# STlink-V3EC.net
KiCad netlist of a schematic drawn in Altium Designer
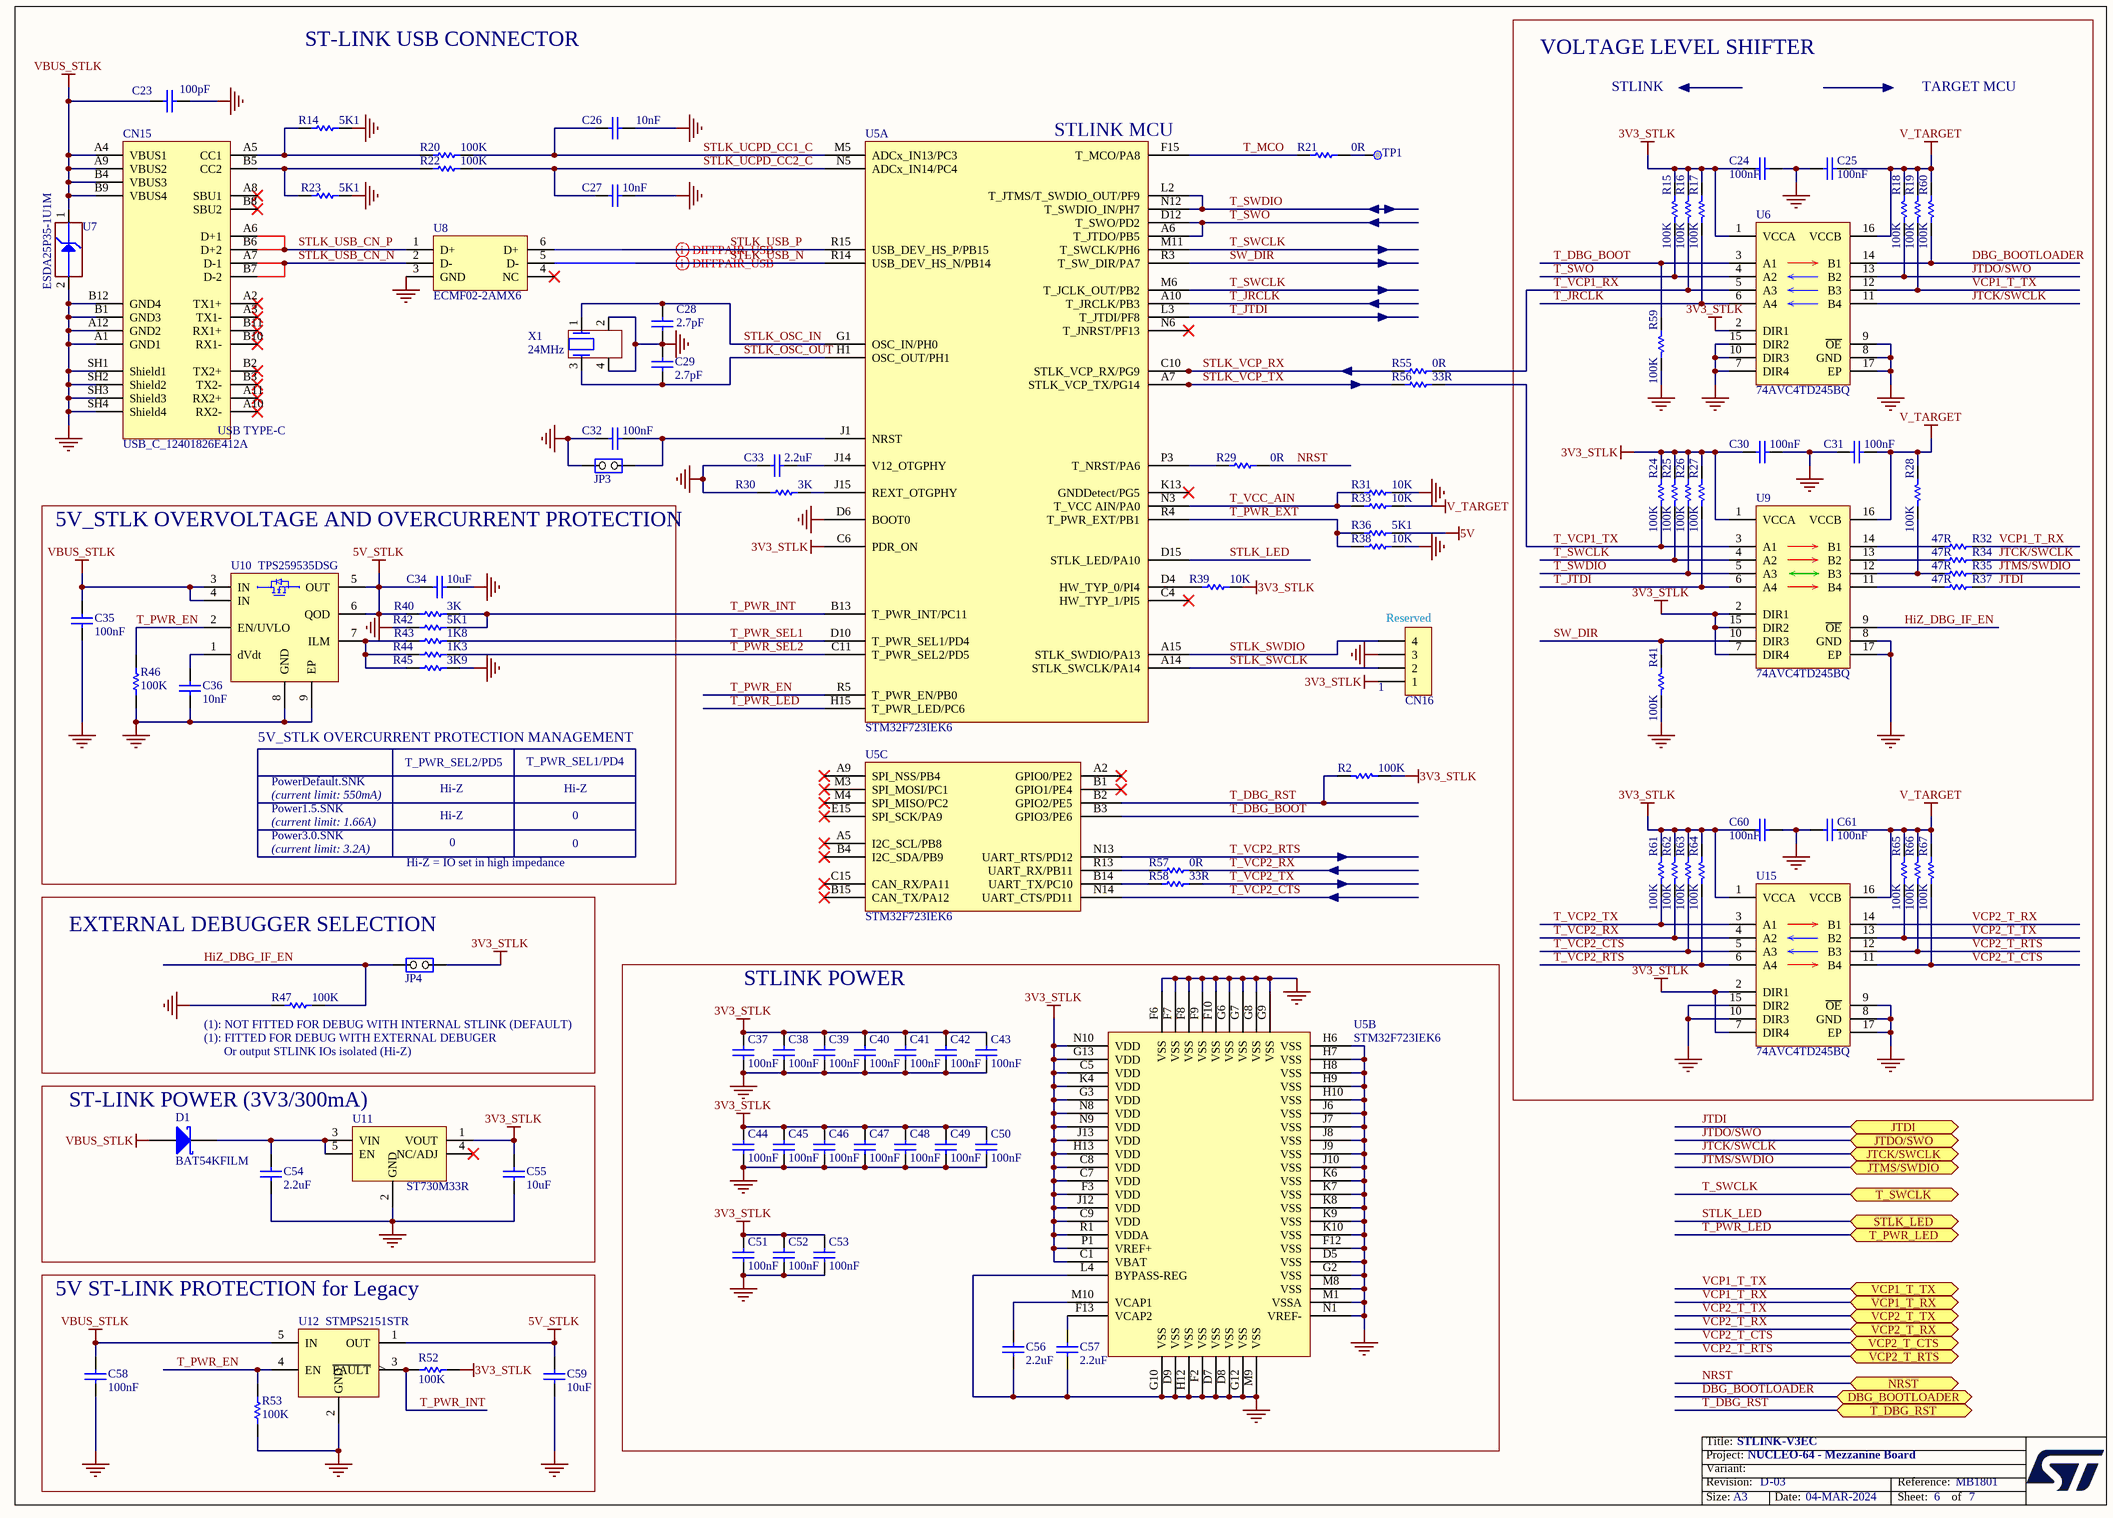
[diagram p0: STlink-V3EC.SchDoc]

(export (version "E")
  (design (tool "Eeschema 10.0.6"))
  (components
    (comp (ref "C23")
      (value "100pF")
      (footprint "MCD_PARTS:C0402")
      (description "Capacitor, MLCC, 100pF, 50V, NPO, +/-5%, 0402, T=0.5mm")
      (fields (field (name "INTERNAL_PART_NUMBER") "MCD-00205") (field (name "MANUFACTURER") "YAGEO"))
      (libsource (lib "MCD_PARTS_database") (part "Capacitor"))
    )
    (comp (ref "C24")
      (value "100nF")
      (footprint "MCD_PARTS:C0402")
      (description "Capacitor, MLCC, 100nF, 16V, X7R, 10%, 0402, T=0.5mm")
      (fields
        (field (name "INTERNAL_PART_NUMBER") "MCD-00006")
        (field (name "MANUFACTURER_PART_NUMBER") "CC0402KRX7R7BB104")
        (field (name "PROVIDED_BY") "SUBCO")
      )
      (libsource (lib "MCD_PARTS_database") (part "Capacitor"))
    )
    (comp (ref "C25")
      (value "100nF")
      (footprint "MCD_PARTS:C0402")
      (description "Capacitor, MLCC, 100nF, 16V, X7R, 10%, 0402, T=0.5mm")
      (fields
        (field (name "INTERNAL_PART_NUMBER") "MCD-00006")
        (field (name "MANUFACTURER_PART_NUMBER") "CC0402KRX7R7BB104")
        (field (name "PROVIDED_BY") "SUBCO")
      )
      (libsource (lib "MCD_PARTS_database") (part "Capacitor"))
    )
    (comp (ref "C26")
      (value "10nF")
      (footprint "MCD_PARTS:C0402")
      (description "Capacitor, MLCC, 10nF, 50V, X7R, +/-10%, 0402, T=0.5mm")
      (fields (field (name "INTERNAL_PART_NUMBER") "MCD-02198") (field (name "MANUFACTURER") "YAGEO"))
      (libsource (lib "MCD_PARTS_database") (part "Capacitor"))
    )
    (comp (ref "C27")
      (value "10nF")
      (footprint "MCD_PARTS:C0402")
      (description "Capacitor, MLCC, 10nF, 50V, X7R, +/-10%, 0402, T=0.5mm")
      (fields (field (name "INTERNAL_PART_NUMBER") "MCD-02198") (field (name "MANUFACTURER") "YAGEO"))
      (libsource (lib "MCD_PARTS_database") (part "Capacitor"))
    )
    (comp (ref "C28")
      (value "2.7pF")
      (footprint "MCD_PARTS:C0402")
      (description "Capacitor, MLCC, 2.7pF, 50V, NPO, +/-0.1pF, 0402, T=0.5mm")
      (fields (field (name "INTERNAL_PART_NUMBER") "MCD-01774") (field (name "MANUFACTURER") "YAGEO"))
      (libsource (lib "MCD_PARTS_database") (part "Capacitor"))
    )
    (comp (ref "C29")
      (value "2.7pF")
      (footprint "MCD_PARTS:C0402")
      (description "Capacitor, MLCC, 2.7pF, 50V, NPO, +/-0.1pF, 0402, T=0.5mm")
      (fields (field (name "INTERNAL_PART_NUMBER") "MCD-01774") (field (name "MANUFACTURER") "YAGEO"))
      (libsource (lib "MCD_PARTS_database") (part "Capacitor"))
    )
    (comp (ref "C30")
      (value "100nF")
      (footprint "MCD_PARTS:C0402")
      (description "Capacitor, MLCC, 100nF, 16V, X7R, 10%, 0402, T=0.5mm")
      (fields
        (field (name "INTERNAL_PART_NUMBER") "MCD-00006")
        (field (name "MANUFACTURER_PART_NUMBER") "CC0402KRX7R7BB104")
        (field (name "PROVIDED_BY") "SUBCO")
      )
      (libsource (lib "MCD_PARTS_database") (part "Capacitor"))
    )
    (comp (ref "C31")
      (value "100nF")
      (footprint "MCD_PARTS:C0402")
      (description "Capacitor, MLCC, 100nF, 16V, X7R, 10%, 0402, T=0.5mm")
      (fields
        (field (name "INTERNAL_PART_NUMBER") "MCD-00006")
        (field (name "MANUFACTURER_PART_NUMBER") "CC0402KRX7R7BB104")
        (field (name "PROVIDED_BY") "SUBCO")
      )
      (libsource (lib "MCD_PARTS_database") (part "Capacitor"))
    )
    (comp (ref "C32")
      (value "100nF")
      (footprint "MCD_PARTS:C0402")
      (description "Capacitor, MLCC, 100nF, 16V, X7R, 10%, 0402, T=0.5mm")
      (fields
        (field (name "INTERNAL_PART_NUMBER") "MCD-00006")
        (field (name "MANUFACTURER_PART_NUMBER") "CC0402KRX7R7BB104")
        (field (name "PROVIDED_BY") "SUBCO")
      )
      (libsource (lib "MCD_PARTS_database") (part "Capacitor"))
    )
    (comp (ref "C33")
      (value "2.2uF")
      (footprint "MCD_PARTS:C0402")
      (description "Capacitor, MLCC, 2.2uF, 6.3V, X5R, +/-10%, 0402, T=0.5mm")
      (fields (field (name "INTERNAL_PART_NUMBER") "MCD-02606") (field (name "MANUFACTURER") "YAGEO"))
      (libsource (lib "MCD_PARTS_database") (part "Capacitor"))
    )
    (comp (ref "C34")
      (value "10uF")
      (footprint "MCD_PARTS:C0603")
      (description "Capacitor, MLCC, 10uF, 10V, X5R, +/-10%, 0603, T=0.8mm")
      (fields (field (name "INTERNAL_PART_NUMBER") "MCD-00099") (field (name "MANUFACTURER") "MURATA"))
      (libsource (lib "MCD_PARTS_database") (part "Capacitor"))
    )
    (comp (ref "C35")
      (value "100nF")
      (footprint "MCD_PARTS:C0402")
      (description "Capacitor, MLCC, 100nF, 25V, X7R, +/-10%, 0402, T=0.5mm")
      (fields (field (name "INTERNAL_PART_NUMBER") "MCD-02355") (field (name "MANUFACTURER") "WALSIN"))
      (libsource (lib "MCD_PARTS_database") (part "Capacitor"))
    )
    (comp (ref "C36")
      (value "10nF")
      (footprint "MCD_PARTS:C0402")
      (description "Capacitor, MLCC, 10nF, 50V, X7R, +/-10%, 0402, T=0.5mm")
      (fields (field (name "INTERNAL_PART_NUMBER") "MCD-02198") (field (name "MANUFACTURER") "YAGEO"))
      (libsource (lib "MCD_PARTS_database") (part "Capacitor"))
    )
    (comp (ref "C37")
      (value "100nF")
      (footprint "MCD_PARTS:C0402")
      (description "Capacitor, MLCC, 100nF, 16V, X7R, 10%, 0402, T=0.5mm")
      (fields
        (field (name "INTERNAL_PART_NUMBER") "MCD-00006")
        (field (name "MANUFACTURER_PART_NUMBER") "CC0402KRX7R7BB104")
        (field (name "PROVIDED_BY") "SUBCO")
      )
      (libsource (lib "MCD_PARTS_database") (part "Capacitor"))
    )
    (comp (ref "C38")
      (value "100nF")
      (footprint "MCD_PARTS:C0402")
      (description "Capacitor, MLCC, 100nF, 16V, X7R, 10%, 0402, T=0.5mm")
      (fields
        (field (name "INTERNAL_PART_NUMBER") "MCD-00006")
        (field (name "MANUFACTURER_PART_NUMBER") "CC0402KRX7R7BB104")
        (field (name "PROVIDED_BY") "SUBCO")
      )
      (libsource (lib "MCD_PARTS_database") (part "Capacitor"))
    )
    (comp (ref "C39")
      (value "100nF")
      (footprint "MCD_PARTS:C0402")
      (description "Capacitor, MLCC, 100nF, 16V, X7R, 10%, 0402, T=0.5mm")
      (fields
        (field (name "INTERNAL_PART_NUMBER") "MCD-00006")
        (field (name "MANUFACTURER_PART_NUMBER") "CC0402KRX7R7BB104")
        (field (name "PROVIDED_BY") "SUBCO")
      )
      (libsource (lib "MCD_PARTS_database") (part "Capacitor"))
    )
    (comp (ref "C40")
      (value "100nF")
      (footprint "MCD_PARTS:C0402")
      (description "Capacitor, MLCC, 100nF, 16V, X7R, 10%, 0402, T=0.5mm")
      (fields
        (field (name "INTERNAL_PART_NUMBER") "MCD-00006")
        (field (name "MANUFACTURER_PART_NUMBER") "CC0402KRX7R7BB104")
        (field (name "PROVIDED_BY") "SUBCO")
      )
      (libsource (lib "MCD_PARTS_database") (part "Capacitor"))
    )
    (comp (ref "C41")
      (value "100nF")
      (footprint "MCD_PARTS:C0402")
      (description "Capacitor, MLCC, 100nF, 16V, X7R, 10%, 0402, T=0.5mm")
      (fields
        (field (name "INTERNAL_PART_NUMBER") "MCD-00006")
        (field (name "MANUFACTURER_PART_NUMBER") "CC0402KRX7R7BB104")
        (field (name "PROVIDED_BY") "SUBCO")
      )
      (libsource (lib "MCD_PARTS_database") (part "Capacitor"))
    )
    (comp (ref "C42")
      (value "100nF")
      (footprint "MCD_PARTS:C0402")
      (description "Capacitor, MLCC, 100nF, 16V, X7R, 10%, 0402, T=0.5mm")
      (fields
        (field (name "INTERNAL_PART_NUMBER") "MCD-00006")
        (field (name "MANUFACTURER_PART_NUMBER") "CC0402KRX7R7BB104")
        (field (name "PROVIDED_BY") "SUBCO")
      )
      (libsource (lib "MCD_PARTS_database") (part "Capacitor"))
    )
    (comp (ref "C43")
      (value "100nF")
      (footprint "MCD_PARTS:C0402")
      (description "Capacitor, MLCC, 100nF, 16V, X7R, 10%, 0402, T=0.5mm")
      (fields
        (field (name "INTERNAL_PART_NUMBER") "MCD-00006")
        (field (name "MANUFACTURER_PART_NUMBER") "CC0402KRX7R7BB104")
        (field (name "PROVIDED_BY") "SUBCO")
      )
      (libsource (lib "MCD_PARTS_database") (part "Capacitor"))
    )
    (comp (ref "C44")
      (value "100nF")
      (footprint "MCD_PARTS:C0402")
      (description "Capacitor, MLCC, 100nF, 16V, X7R, 10%, 0402, T=0.5mm")
      (fields
        (field (name "INTERNAL_PART_NUMBER") "MCD-00006")
        (field (name "MANUFACTURER_PART_NUMBER") "CC0402KRX7R7BB104")
        (field (name "PROVIDED_BY") "SUBCO")
      )
      (libsource (lib "MCD_PARTS_database") (part "Capacitor"))
    )
    (comp (ref "C45")
      (value "100nF")
      (footprint "MCD_PARTS:C0402")
      (description "Capacitor, MLCC, 100nF, 16V, X7R, 10%, 0402, T=0.5mm")
      (fields
        (field (name "INTERNAL_PART_NUMBER") "MCD-00006")
        (field (name "MANUFACTURER_PART_NUMBER") "CC0402KRX7R7BB104")
        (field (name "PROVIDED_BY") "SUBCO")
      )
      (libsource (lib "MCD_PARTS_database") (part "Capacitor"))
    )
    (comp (ref "C46")
      (value "100nF")
      (footprint "MCD_PARTS:C0402")
      (description "Capacitor, MLCC, 100nF, 16V, X7R, 10%, 0402, T=0.5mm")
      (fields
        (field (name "INTERNAL_PART_NUMBER") "MCD-00006")
        (field (name "MANUFACTURER_PART_NUMBER") "CC0402KRX7R7BB104")
        (field (name "PROVIDED_BY") "SUBCO")
      )
      (libsource (lib "MCD_PARTS_database") (part "Capacitor"))
    )
    (comp (ref "C47")
      (value "100nF")
      (footprint "MCD_PARTS:C0402")
      (description "Capacitor, MLCC, 100nF, 16V, X7R, 10%, 0402, T=0.5mm")
      (fields
        (field (name "INTERNAL_PART_NUMBER") "MCD-00006")
        (field (name "MANUFACTURER_PART_NUMBER") "CC0402KRX7R7BB104")
        (field (name "PROVIDED_BY") "SUBCO")
      )
      (libsource (lib "MCD_PARTS_database") (part "Capacitor"))
    )
    (comp (ref "C48")
      (value "100nF")
      (footprint "MCD_PARTS:C0402")
      (description "Capacitor, MLCC, 100nF, 16V, X7R, 10%, 0402, T=0.5mm")
      (fields
        (field (name "INTERNAL_PART_NUMBER") "MCD-00006")
        (field (name "MANUFACTURER_PART_NUMBER") "CC0402KRX7R7BB104")
        (field (name "PROVIDED_BY") "SUBCO")
      )
      (libsource (lib "MCD_PARTS_database") (part "Capacitor"))
    )
    (comp (ref "C49")
      (value "100nF")
      (footprint "MCD_PARTS:C0402")
      (description "Capacitor, MLCC, 100nF, 16V, X7R, 10%, 0402, T=0.5mm")
      (fields
        (field (name "INTERNAL_PART_NUMBER") "MCD-00006")
        (field (name "MANUFACTURER_PART_NUMBER") "CC0402KRX7R7BB104")
        (field (name "PROVIDED_BY") "SUBCO")
      )
      (libsource (lib "MCD_PARTS_database") (part "Capacitor"))
    )
    (comp (ref "C50")
      (value "100nF")
      (footprint "MCD_PARTS:C0402")
      (description "Capacitor, MLCC, 100nF, 16V, X7R, 10%, 0402, T=0.5mm")
      (fields
        (field (name "INTERNAL_PART_NUMBER") "MCD-00006")
        (field (name "MANUFACTURER_PART_NUMBER") "CC0402KRX7R7BB104")
        (field (name "PROVIDED_BY") "SUBCO")
      )
      (libsource (lib "MCD_PARTS_database") (part "Capacitor"))
    )
    (comp (ref "C51")
      (value "100nF")
      (footprint "MCD_PARTS:C0402")
      (description "Capacitor, MLCC, 100nF, 16V, X7R, 10%, 0402, T=0.5mm")
      (fields
        (field (name "INTERNAL_PART_NUMBER") "MCD-00006")
        (field (name "MANUFACTURER_PART_NUMBER") "CC0402KRX7R7BB104")
        (field (name "PROVIDED_BY") "SUBCO")
      )
      (libsource (lib "MCD_PARTS_database") (part "Capacitor"))
    )
    (comp (ref "C52")
      (value "100nF")
      (footprint "MCD_PARTS:C0402")
      (description "Capacitor, MLCC, 100nF, 16V, X7R, 10%, 0402, T=0.5mm")
      (fields
        (field (name "INTERNAL_PART_NUMBER") "MCD-00006")
        (field (name "MANUFACTURER_PART_NUMBER") "CC0402KRX7R7BB104")
        (field (name "PROVIDED_BY") "SUBCO")
      )
      (libsource (lib "MCD_PARTS_database") (part "Capacitor"))
    )
    (comp (ref "C53")
      (value "100nF")
      (footprint "MCD_PARTS:C0402")
      (description "Capacitor, MLCC, 100nF, 16V, X7R, 10%, 0402, T=0.5mm")
      (fields
        (field (name "INTERNAL_PART_NUMBER") "MCD-00006")
        (field (name "MANUFACTURER_PART_NUMBER") "CC0402KRX7R7BB104")
        (field (name "PROVIDED_BY") "SUBCO")
      )
      (libsource (lib "MCD_PARTS_database") (part "Capacitor"))
    )
    (comp (ref "C54")
      (value "2.2uF")
      (footprint "MCD_PARTS:C0805")
      (description "Capacitor, MLCC, 2.2uF, 25V, X7R, +/-10%, 0805, T=1,25mm")
      (fields
        (field (name "INTERNAL_PART_NUMBER") "MCD-02372")
        (field (name "MANUFACTURER_PART_NUMBER") "GRM21BR71E225KE11L")
        (field (name "PROVIDED_BY") "SUBCO")
      )
      (libsource (lib "MCD_PARTS_database") (part "Capacitor"))
    )
    (comp (ref "C55")
      (value "10uF")
      (footprint "MCD_PARTS:C0603")
      (description "Capacitor, MLCC, 10uF, 10V, X5R, +/-10%, 0603, T=0.8mm")
      (fields (field (name "INTERNAL_PART_NUMBER") "MCD-00099") (field (name "MANUFACTURER") "MURATA"))
      (libsource (lib "MCD_PARTS_database") (part "Capacitor"))
    )
    (comp (ref "C56")
      (value "2.2uF")
      (footprint "MCD_PARTS:C0402")
      (description "Capacitor, MLCC, 2.2uF, 6.3V, X5R, +/-10%, 0402, T=0.5mm")
      (fields (field (name "INTERNAL_PART_NUMBER") "MCD-02606") (field (name "MANUFACTURER") "YAGEO"))
      (libsource (lib "MCD_PARTS_database") (part "Capacitor"))
    )
    (comp (ref "C57")
      (value "2.2uF")
      (footprint "MCD_PARTS:C0402")
      (description "Capacitor, MLCC, 2.2uF, 6.3V, X5R, +/-10%, 0402, T=0.5mm")
      (fields (field (name "INTERNAL_PART_NUMBER") "MCD-02606") (field (name "MANUFACTURER") "YAGEO"))
      (libsource (lib "MCD_PARTS_database") (part "Capacitor"))
    )
    (comp (ref "C58")
      (value "100nF")
      (footprint "MCD_PARTS:C0402")
      (description "Capacitor, MLCC, 100nF, 25V, X7R, +/-10%, 0402, T=0.5mm")
      (fields (field (name "INTERNAL_PART_NUMBER") "MCD-02355") (field (name "MANUFACTURER") "WALSIN"))
      (libsource (lib "MCD_PARTS_database") (part "Capacitor"))
    )
    (comp (ref "C59")
      (value "10uF")
      (footprint "MCD_PARTS:C0603")
      (description "Capacitor, MLCC, 10uF, 10V, X5R, +/-10%, 0603, T=0.8mm")
      (fields (field (name "INTERNAL_PART_NUMBER") "MCD-00099") (field (name "MANUFACTURER") "MURATA"))
      (libsource (lib "MCD_PARTS_database") (part "Capacitor"))
    )
    (comp (ref "C60")
      (value "100nF")
      (footprint "MCD_PARTS:C0402")
      (description "Capacitor, MLCC, 100nF, 16V, X7R, 10%, 0402, T=0.5mm")
      (fields
        (field (name "INTERNAL_PART_NUMBER") "MCD-00006")
        (field (name "MANUFACTURER_PART_NUMBER") "CC0402KRX7R7BB104")
        (field (name "PROVIDED_BY") "SUBCO")
      )
      (libsource (lib "MCD_PARTS_database") (part "Capacitor"))
    )
    (comp (ref "C61")
      (value "100nF")
      (footprint "MCD_PARTS:C0402")
      (description "Capacitor, MLCC, 100nF, 16V, X7R, 10%, 0402, T=0.5mm")
      (fields
        (field (name "INTERNAL_PART_NUMBER") "MCD-00006")
        (field (name "MANUFACTURER_PART_NUMBER") "CC0402KRX7R7BB104")
        (field (name "PROVIDED_BY") "SUBCO")
      )
      (libsource (lib "MCD_PARTS_database") (part "Capacitor"))
    )
    (comp (ref "CN15")
      (value "USB_C_12401826E412A")
      (footprint "MCD_PARTS:CON_USB-TYPEC_AMPHENOL_12401826E412A")
      (description "USB_TypeC, 24 pins, RA, SMD, T=2.96mm")
      (fields (field (name "INTERNAL_PART_NUMBER") "MCD-03232") (field (name "MANUFACTURER") "AMPHENOL ICC"))
      (libsource (lib "MCD_PARTS_database") (part "USB_TYPE_C_Receptacle"))
    )
    (comp (ref "CN16")
      (value "Header 4x1")
      (footprint "MCD_PARTS:CON_SAMTEC_TSW-104-07-G-S")
      (description "Header, 4x1, 2,54mm, VR, TH, Height 5.84mm/2.54mm")
      (fields
        (field (name "INTERNAL_PART_NUMBER") "MCD-00029")
        (field (name "MANUFACTURER_PART_NUMBER") "TSW-104-07-x-S")
        (field (name "PROVIDED_BY") "SUBCO")
      )
      (libsource (lib "MCD_PARTS_database") (part "Header 4x1"))
    )
    (comp (ref "D1")
      (value "BAT54KFILM")
      (footprint "MCD_PARTS:DIO_SOD523_1A_2K")
      (description "Small signal Schottky diodes")
      (fields (field (name "INTERNAL_PART_NUMBER") "MCD-01677") (field (name "BMS_PART_NUMBER") "9151123"))
      (libsource (lib "MCD_PARTS_database") (part "SCHOTTKY_1A_2K"))
    )
    (comp (ref "JP3")
      (value "Jumper_Header 2x1")
      (footprint "MCD_PARTS:CON_SAMTEC_TSW-102-07-G-S")
      (description "Header, 2x1, 2,54mm, VR, TH, Height 5.84mm/2.54mm")
      (fields (field (name "INTERNAL_PART_NUMBER") "MCD-00045") (field (name "MANUFACTURER") "SAMTEC"))
      (libsource (lib "MCD_PARTS_database") (part "Jumper_Header 2x1"))
    )
    (comp (ref "JP4")
      (value "Jumper_Header 2x1")
      (footprint "MCD_PARTS:CON_SAMTEC_TSW-102-07-G-S")
      (description "Header, 2x1, 2,54mm, VR, TH, Height 5.84mm/2.54mm")
      (fields (field (name "INTERNAL_PART_NUMBER") "MCD-00045") (field (name "MANUFACTURER") "SAMTEC"))
      (libsource (lib "MCD_PARTS_database") (part "Jumper_Header 2x1"))
    )
    (comp (ref "R2")
      (value "100K")
      (footprint "MCD_PARTS:R0402")
      (description "Resistor,100K,0402,1%,1/16W")
      (fields
        (field (name "INTERNAL_PART_NUMBER") "MCD-00059")
        (field (name "MANUFACTURER_PART_NUMBER") "RC0402FR-07100KL")
        (field (name "PROVIDED_BY") "Subcon")
      )
      (libsource (lib "MCD_PARTS_database") (part "Resistor"))
    )
    (comp (ref "R14")
      (value "5K1")
      (footprint "MCD_PARTS:R0402")
      (description "Resistor, 5K1, 0402, +/-1%, 1/16W")
      (fields (field (name "INTERNAL_PART_NUMBER") "MCD-00333") (field (name "MANUFACTURER") "YAGEO"))
      (libsource (lib "MCD_PARTS_database") (part "Resistor"))
    )
    (comp (ref "R15")
      (value "100K")
      (footprint "MCD_PARTS:R0402")
      (description "Resistor,100K,0402,1%,1/16W")
      (fields
        (field (name "INTERNAL_PART_NUMBER") "MCD-00059")
        (field (name "MANUFACTURER_PART_NUMBER") "RC0402FR-07100KL")
        (field (name "PROVIDED_BY") "Subcon")
      )
      (libsource (lib "MCD_PARTS_database") (part "Resistor"))
    )
    (comp (ref "R16")
      (value "100K")
      (footprint "MCD_PARTS:R0402")
      (description "Resistor,100K,0402,1%,1/16W")
      (fields
        (field (name "INTERNAL_PART_NUMBER") "MCD-00059")
        (field (name "MANUFACTURER_PART_NUMBER") "RC0402FR-07100KL")
        (field (name "PROVIDED_BY") "Subcon")
      )
      (libsource (lib "MCD_PARTS_database") (part "Resistor"))
    )
    (comp (ref "R17")
      (value "100K")
      (footprint "MCD_PARTS:R0402")
      (description "Resistor,100K,0402,1%,1/16W")
      (fields
        (field (name "INTERNAL_PART_NUMBER") "MCD-00059")
        (field (name "MANUFACTURER_PART_NUMBER") "RC0402FR-07100KL")
        (field (name "PROVIDED_BY") "Subcon")
      )
      (libsource (lib "MCD_PARTS_database") (part "Resistor"))
    )
    (comp (ref "R18")
      (value "100K")
      (footprint "MCD_PARTS:R0402")
      (description "Resistor,100K,0402,1%,1/16W")
      (fields
        (field (name "INTERNAL_PART_NUMBER") "MCD-00059")
        (field (name "MANUFACTURER_PART_NUMBER") "RC0402FR-07100KL")
        (field (name "PROVIDED_BY") "Subcon")
      )
      (libsource (lib "MCD_PARTS_database") (part "Resistor"))
    )
    (comp (ref "R19")
      (value "100K")
      (footprint "MCD_PARTS:R0402")
      (description "Resistor,100K,0402,1%,1/16W")
      (fields
        (field (name "INTERNAL_PART_NUMBER") "MCD-00059")
        (field (name "MANUFACTURER_PART_NUMBER") "RC0402FR-07100KL")
        (field (name "PROVIDED_BY") "Subcon")
      )
      (libsource (lib "MCD_PARTS_database") (part "Resistor"))
    )
    (comp (ref "R20")
      (value "100K")
      (footprint "MCD_PARTS:R0402")
      (description "Resistor, 100K, 0402, +/-1%, 1/16W")
      (fields (field (name "INTERNAL_PART_NUMBER") "MCD-00059") (field (name "MANUFACTURER") "YAGEO"))
      (libsource (lib "MCD_PARTS_database") (part "Resistor"))
    )
    (comp (ref "R21")
      (value "0R")
      (footprint "MCD_PARTS:R0402")
      (description "Resistor, 0R, 0402, +/-5%, 1/16W")
      (fields (field (name "INTERNAL_PART_NUMBER") "MCD-00052") (field (name "MANUFACTURER") "YAGEO"))
      (libsource (lib "MCD_PARTS_database") (part "Resistor"))
    )
    (comp (ref "R22")
      (value "100K")
      (footprint "MCD_PARTS:R0402")
      (description "Resistor, 100K, 0402, +/-1%, 1/16W")
      (fields (field (name "INTERNAL_PART_NUMBER") "MCD-00059") (field (name "MANUFACTURER") "YAGEO"))
      (libsource (lib "MCD_PARTS_database") (part "Resistor"))
    )
    (comp (ref "R23")
      (value "5K1")
      (footprint "MCD_PARTS:R0402")
      (description "Resistor, 5K1, 0402, +/-1%, 1/16W")
      (fields (field (name "INTERNAL_PART_NUMBER") "MCD-00333") (field (name "MANUFACTURER") "YAGEO"))
      (libsource (lib "MCD_PARTS_database") (part "Resistor"))
    )
    (comp (ref "R24")
      (value "100K")
      (footprint "MCD_PARTS:R0402")
      (description "Resistor,100K,0402,1%,1/16W")
      (fields
        (field (name "INTERNAL_PART_NUMBER") "MCD-00059")
        (field (name "MANUFACTURER_PART_NUMBER") "RC0402FR-07100KL")
        (field (name "PROVIDED_BY") "Subcon")
      )
      (libsource (lib "MCD_PARTS_database") (part "Resistor"))
    )
    (comp (ref "R25")
      (value "100K")
      (footprint "MCD_PARTS:R0402")
      (description "Resistor,100K,0402,1%,1/16W")
      (fields
        (field (name "INTERNAL_PART_NUMBER") "MCD-00059")
        (field (name "MANUFACTURER_PART_NUMBER") "RC0402FR-07100KL")
        (field (name "PROVIDED_BY") "Subcon")
      )
      (libsource (lib "MCD_PARTS_database") (part "Resistor"))
    )
    (comp (ref "R26")
      (value "100K")
      (footprint "MCD_PARTS:R0402")
      (description "Resistor,100K,0402,1%,1/16W")
      (fields
        (field (name "INTERNAL_PART_NUMBER") "MCD-00059")
        (field (name "MANUFACTURER_PART_NUMBER") "RC0402FR-07100KL")
        (field (name "PROVIDED_BY") "Subcon")
      )
      (libsource (lib "MCD_PARTS_database") (part "Resistor"))
    )
    (comp (ref "R27")
      (value "100K")
      (footprint "MCD_PARTS:R0402")
      (description "Resistor,100K,0402,1%,1/16W")
      (fields
        (field (name "INTERNAL_PART_NUMBER") "MCD-00059")
        (field (name "MANUFACTURER_PART_NUMBER") "RC0402FR-07100KL")
        (field (name "PROVIDED_BY") "Subcon")
      )
      (libsource (lib "MCD_PARTS_database") (part "Resistor"))
    )
    (comp (ref "R28")
      (value "100K")
      (footprint "MCD_PARTS:R0402")
      (description "Resistor,100K,0402,1%,1/16W")
      (fields
        (field (name "INTERNAL_PART_NUMBER") "MCD-00059")
        (field (name "MANUFACTURER_PART_NUMBER") "RC0402FR-07100KL")
        (field (name "PROVIDED_BY") "Subcon")
      )
      (libsource (lib "MCD_PARTS_database") (part "Resistor"))
    )
    (comp (ref "R29")
      (value "0R")
      (footprint "MCD_PARTS:R0402")
      (description "Resistor, 0R, 0402, +/-5%, 1/16W")
      (fields (field (name "INTERNAL_PART_NUMBER") "MCD-00052") (field (name "MANUFACTURER") "YAGEO"))
      (libsource (lib "MCD_PARTS_database") (part "Resistor"))
    )
    (comp (ref "R30")
      (value "3K")
      (footprint "MCD_PARTS:R0402")
      (description "Resistor,3K,0402,1%,1/16W")
      (fields
        (field (name "INTERNAL_PART_NUMBER") "MCD-00185")
        (field (name "MANUFACTURER_PART_NUMBER") "RC0402FR-073KL")
        (field (name "PROVIDED_BY") "SUBCO")
      )
      (libsource (lib "MCD_PARTS_database") (part "Resistor"))
    )
    (comp (ref "R31")
      (value "10K")
      (footprint "MCD_PARTS:R0402")
      (description "Resistor,10K,0402,1%,1/16W")
      (fields
        (field (name "INTERNAL_PART_NUMBER") "MCD-00053")
        (field (name "MANUFACTURER_PART_NUMBER") "RC0402FR-0710KL")
        (field (name "PROVIDED_BY") "SUBCO")
      )
      (libsource (lib "MCD_PARTS_database") (part "Resistor"))
    )
    (comp (ref "R32")
      (value "47R")
      (footprint "MCD_PARTS:R0402")
      (description "Resistor,47R,0402,1%,1/16W")
      (fields
        (field (name "INTERNAL_PART_NUMBER") "MCD-00481")
        (field (name "MANUFACTURER_PART_NUMBER") "RC0402FR-0747RL")
        (field (name "PROVIDED_BY") "SUBCO")
      )
      (libsource (lib "MCD_PARTS_database") (part "Resistor"))
    )
    (comp (ref "R33")
      (value "10K")
      (footprint "MCD_PARTS:R0402")
      (description "Resistor,10K,0402,1%,1/16W")
      (fields
        (field (name "INTERNAL_PART_NUMBER") "MCD-00053")
        (field (name "MANUFACTURER_PART_NUMBER") "RC0402FR-0710KL")
        (field (name "PROVIDED_BY") "SUBCO")
      )
      (libsource (lib "MCD_PARTS_database") (part "Resistor"))
    )
    (comp (ref "R34")
      (value "47R")
      (footprint "MCD_PARTS:R0402")
      (description "Resistor,47R,0402,1%,1/16W")
      (fields
        (field (name "INTERNAL_PART_NUMBER") "MCD-00481")
        (field (name "MANUFACTURER_PART_NUMBER") "RC0402FR-0747RL")
        (field (name "PROVIDED_BY") "SUBCO")
      )
      (libsource (lib "MCD_PARTS_database") (part "Resistor"))
    )
    (comp (ref "R35")
      (value "47R")
      (footprint "MCD_PARTS:R0402")
      (description "Resistor,47R,0402,1%,1/16W")
      (fields
        (field (name "INTERNAL_PART_NUMBER") "MCD-00481")
        (field (name "MANUFACTURER_PART_NUMBER") "RC0402FR-0747RL")
        (field (name "PROVIDED_BY") "SUBCO")
      )
      (libsource (lib "MCD_PARTS_database") (part "Resistor"))
    )
    (comp (ref "R36")
      (value "5K1")
      (footprint "MCD_PARTS:R0402")
      (description "Resistor, 5K1, 0402, +/-1%, 1/16W")
      (fields (field (name "INTERNAL_PART_NUMBER") "MCD-00333") (field (name "MANUFACTURER") "YAGEO"))
      (libsource (lib "MCD_PARTS_database") (part "Resistor"))
    )
    (comp (ref "R37")
      (value "47R")
      (footprint "MCD_PARTS:R0402")
      (description "Resistor,47R,0402,1%,1/16W")
      (fields
        (field (name "INTERNAL_PART_NUMBER") "MCD-00481")
        (field (name "MANUFACTURER_PART_NUMBER") "RC0402FR-0747RL")
        (field (name "PROVIDED_BY") "SUBCO")
      )
      (libsource (lib "MCD_PARTS_database") (part "Resistor"))
    )
    (comp (ref "R38")
      (value "10K")
      (footprint "MCD_PARTS:R0402")
      (description "Resistor,10K,0402,1%,1/16W")
      (fields
        (field (name "INTERNAL_PART_NUMBER") "MCD-00053")
        (field (name "MANUFACTURER_PART_NUMBER") "RC0402FR-0710KL")
        (field (name "PROVIDED_BY") "SUBCO")
      )
      (libsource (lib "MCD_PARTS_database") (part "Resistor"))
    )
    (comp (ref "R39")
      (value "10K")
      (footprint "MCD_PARTS:R0402")
      (description "Resistor,10K,0402,1%,1/16W")
      (fields
        (field (name "INTERNAL_PART_NUMBER") "MCD-00053")
        (field (name "MANUFACTURER_PART_NUMBER") "RC0402FR-0710KL")
        (field (name "PROVIDED_BY") "SUBCO")
      )
      (libsource (lib "MCD_PARTS_database") (part "Resistor"))
    )
    (comp (ref "R40")
      (value "3K")
      (footprint "MCD_PARTS:R0402")
      (description "Resistor, 3K, 0402, +/-1%, 1/16W")
      (fields (field (name "INTERNAL_PART_NUMBER") "MCD-00185") (field (name "MANUFACTURER") "YAGEO"))
      (libsource (lib "MCD_PARTS_database") (part "Resistor"))
    )
    (comp (ref "R41")
      (value "100K")
      (footprint "MCD_PARTS:R0402")
      (description "Resistor,100K,0402,1%,1/16W")
      (fields
        (field (name "INTERNAL_PART_NUMBER") "MCD-00059")
        (field (name "MANUFACTURER_PART_NUMBER") "RC0402FR-07100KL")
        (field (name "PROVIDED_BY") "Subcon")
      )
      (libsource (lib "MCD_PARTS_database") (part "Resistor"))
    )
    (comp (ref "R42")
      (value "5K1")
      (footprint "MCD_PARTS:R0402")
      (description "Resistor, 5K1, 0402, +/-1%, 1/16W")
      (fields (field (name "INTERNAL_PART_NUMBER") "MCD-00333") (field (name "MANUFACTURER") "YAGEO"))
      (libsource (lib "MCD_PARTS_database") (part "Resistor"))
    )
    (comp (ref "R43")
      (value "1K8")
      (footprint "MCD_PARTS:R0402")
      (description "Resistor, 1K8, 0402, +/-1%, 1/16W")
      (fields (field (name "INTERNAL_PART_NUMBER") "MCD-00409") (field (name "MANUFACTURER") "YAGEO"))
      (libsource (lib "MCD_PARTS_database") (part "Resistor"))
    )
    (comp (ref "R44")
      (value "1K3")
      (footprint "MCD_PARTS:R0402")
      (description "Resistor, 1K3, 0402, +/-1%, 1/16W")
      (fields (field (name "INTERNAL_PART_NUMBER") "MCD-00381") (field (name "MANUFACTURER") "YAGEO"))
      (libsource (lib "MCD_PARTS_database") (part "Resistor"))
    )
    (comp (ref "R45")
      (value "3K9")
      (footprint "MCD_PARTS:R0402")
      (description "Resistor, 3K9, 0402, +/-1%, 1/16W, +/-100ppm/°C")
      (fields (field (name "INTERNAL_PART_NUMBER") "MCD-02455") (field (name "MANUFACTURER") "YAGEO"))
      (libsource (lib "MCD_PARTS_database") (part "Resistor"))
    )
    (comp (ref "R46")
      (value "100K")
      (footprint "MCD_PARTS:R0402")
      (description "Resistor, 100K, 0402, +/-1%, 1/16W")
      (fields (field (name "INTERNAL_PART_NUMBER") "MCD-00059") (field (name "MANUFACTURER") "YAGEO"))
      (libsource (lib "MCD_PARTS_database") (part "Resistor"))
    )
    (comp (ref "R47")
      (value "100K")
      (footprint "MCD_PARTS:R0402")
      (description "Resistor, 100K, 0402, +/-1%, 1/16W")
      (fields (field (name "INTERNAL_PART_NUMBER") "MCD-00059") (field (name "MANUFACTURER") "YAGEO"))
      (libsource (lib "MCD_PARTS_database") (part "Resistor"))
    )
    (comp (ref "R52")
      (value "100K")
      (footprint "MCD_PARTS:R0402")
      (description "Resistor, 100K, 0402, +/-1%, 1/16W")
      (fields (field (name "INTERNAL_PART_NUMBER") "MCD-00059") (field (name "MANUFACTURER") "YAGEO"))
      (libsource (lib "MCD_PARTS_database") (part "Resistor"))
    )
    (comp (ref "R53")
      (value "100K")
      (footprint "MCD_PARTS:R0402")
      (description "Resistor, 100K, 0402, +/-1%, 1/16W")
      (fields (field (name "INTERNAL_PART_NUMBER") "MCD-00059") (field (name "MANUFACTURER") "YAGEO"))
      (libsource (lib "MCD_PARTS_database") (part "Resistor"))
    )
    (comp (ref "R55")
      (value "0R")
      (footprint "MCD_PARTS:R0402")
      (description "Resistor, 0R, 0402, +/-5%, 1/16W")
      (fields (field (name "INTERNAL_PART_NUMBER") "MCD-00052") (field (name "MANUFACTURER") "YAGEO"))
      (libsource (lib "MCD_PARTS_database") (part "Resistor"))
    )
    (comp (ref "R56")
      (value "33R")
      (footprint "MCD_PARTS:R0402")
      (description "Resistor, 33R, 0402, +/-1%, 1/16W")
      (fields (field (name "INTERNAL_PART_NUMBER") "MCD-00455") (field (name "MANUFACTURER") "YAGEO"))
      (libsource (lib "MCD_PARTS_database") (part "Resistor"))
    )
    (comp (ref "R57")
      (value "0R")
      (footprint "MCD_PARTS:R0402")
      (description "Resistor, 0R, 0402, +/-5%, 1/16W")
      (fields (field (name "INTERNAL_PART_NUMBER") "MCD-00052") (field (name "MANUFACTURER") "YAGEO"))
      (libsource (lib "MCD_PARTS_database") (part "Resistor"))
    )
    (comp (ref "R58")
      (value "33R")
      (footprint "MCD_PARTS:R0402")
      (description "Resistor, 33R, 0402, +/-1%, 1/16W")
      (fields (field (name "INTERNAL_PART_NUMBER") "MCD-00455") (field (name "MANUFACTURER") "YAGEO"))
      (libsource (lib "MCD_PARTS_database") (part "Resistor"))
    )
    (comp (ref "R59")
      (value "100K")
      (footprint "MCD_PARTS:R0402")
      (description "Resistor,100K,0402,1%,1/16W")
      (fields
        (field (name "INTERNAL_PART_NUMBER") "MCD-00059")
        (field (name "MANUFACTURER_PART_NUMBER") "RC0402FR-07100KL")
        (field (name "PROVIDED_BY") "Subcon")
      )
      (libsource (lib "MCD_PARTS_database") (part "Resistor"))
    )
    (comp (ref "R60")
      (value "100K")
      (footprint "MCD_PARTS:R0402")
      (description "Resistor,100K,0402,1%,1/16W")
      (fields
        (field (name "INTERNAL_PART_NUMBER") "MCD-00059")
        (field (name "MANUFACTURER_PART_NUMBER") "RC0402FR-07100KL")
        (field (name "PROVIDED_BY") "Subcon")
      )
      (libsource (lib "MCD_PARTS_database") (part "Resistor"))
    )
    (comp (ref "R61")
      (value "100K")
      (footprint "MCD_PARTS:R0402")
      (description "Resistor,100K,0402,1%,1/16W")
      (fields
        (field (name "INTERNAL_PART_NUMBER") "MCD-00059")
        (field (name "MANUFACTURER_PART_NUMBER") "RC0402FR-07100KL")
        (field (name "PROVIDED_BY") "Subcon")
      )
      (libsource (lib "MCD_PARTS_database") (part "Resistor"))
    )
    (comp (ref "R62")
      (value "100K")
      (footprint "MCD_PARTS:R0402")
      (description "Resistor,100K,0402,1%,1/16W")
      (fields
        (field (name "INTERNAL_PART_NUMBER") "MCD-00059")
        (field (name "MANUFACTURER_PART_NUMBER") "RC0402FR-07100KL")
        (field (name "PROVIDED_BY") "Subcon")
      )
      (libsource (lib "MCD_PARTS_database") (part "Resistor"))
    )
    (comp (ref "R63")
      (value "100K")
      (footprint "MCD_PARTS:R0402")
      (description "Resistor,100K,0402,1%,1/16W")
      (fields
        (field (name "INTERNAL_PART_NUMBER") "MCD-00059")
        (field (name "MANUFACTURER_PART_NUMBER") "RC0402FR-07100KL")
        (field (name "PROVIDED_BY") "Subcon")
      )
      (libsource (lib "MCD_PARTS_database") (part "Resistor"))
    )
    (comp (ref "R64")
      (value "100K")
      (footprint "MCD_PARTS:R0402")
      (description "Resistor,100K,0402,1%,1/16W")
      (fields
        (field (name "INTERNAL_PART_NUMBER") "MCD-00059")
        (field (name "MANUFACTURER_PART_NUMBER") "RC0402FR-07100KL")
        (field (name "PROVIDED_BY") "Subcon")
      )
      (libsource (lib "MCD_PARTS_database") (part "Resistor"))
    )
    (comp (ref "R65")
      (value "100K")
      (footprint "MCD_PARTS:R0402")
      (description "Resistor,100K,0402,1%,1/16W")
      (fields
        (field (name "INTERNAL_PART_NUMBER") "MCD-00059")
        (field (name "MANUFACTURER_PART_NUMBER") "RC0402FR-07100KL")
        (field (name "PROVIDED_BY") "Subcon")
      )
      (libsource (lib "MCD_PARTS_database") (part "Resistor"))
    )
    (comp (ref "R66")
      (value "100K")
      (footprint "MCD_PARTS:R0402")
      (description "Resistor,100K,0402,1%,1/16W")
      (fields
        (field (name "INTERNAL_PART_NUMBER") "MCD-00059")
        (field (name "MANUFACTURER_PART_NUMBER") "RC0402FR-07100KL")
        (field (name "PROVIDED_BY") "Subcon")
      )
      (libsource (lib "MCD_PARTS_database") (part "Resistor"))
    )
    (comp (ref "R67")
      (value "100K")
      (footprint "MCD_PARTS:R0402")
      (description "Resistor,100K,0402,1%,1/16W")
      (fields
        (field (name "INTERNAL_PART_NUMBER") "MCD-00059")
        (field (name "MANUFACTURER_PART_NUMBER") "RC0402FR-07100KL")
        (field (name "PROVIDED_BY") "Subcon")
      )
      (libsource (lib "MCD_PARTS_database") (part "Resistor"))
    )
    (comp (ref "TP1")
      (value "Test Point")
      (footprint "MCD_PARTS:TP_SMD_1MM")
      (description "Test Point 1mm")
      (fields
        (field (name "INTERNAL_PART_NUMBER") "MCD-00074")
        (field (name "MANUFACTURER_PART_NUMBER") "n/a")
      )
      (libsource (lib "MCD_PARTS_database") (part "Test Point"))
    )
    (comp (ref "U5")
      (value "STM32F723IEK6")
      (footprint "ICC_UFBGA201_176+25_10X10_P065")
      (description "MCU, ARM Cortex-M7 32-bit, 512KB Flash, 276KB RAM, With Crypto")
      (fields (field (name "INTERNAL_PART_NUMBER") "MCD-02706") (field (name "BMS_PART_NUMBER") "9175300"))
      (libsource (lib "MCD_PARTS_database") (part "STLINK-V3EC_Old"))
    )
    (comp (ref "U6")
      (value "74AVC4TD245BQ")
      (footprint "MCD_PARTS:ICC_DHVQFN16-EPAD_SOT763-1_2P5X3P5_H0P85_P050")
      (description "4-bit dual supply translating transceiver with configurable voltage translation; 3-state")
      (fields
        (field (name "INTERNAL_PART_NUMBER") "MCD-01945")
        (field (name "MANUFACTURER_PART_NUMBER") "74AVC4TD245BQ,115")
      )
      (libsource (lib "MCD_PARTS_database") (part "74AVC4TD245BQ"))
    )
    (comp (ref "U7")
      (value "ESDA25P35-1U1M")
      (footprint "MCD_PARTS:ESD_QFN1610_2N_1K_2A")
      (description "High power Transient voltage suppressor:25V/35A EOS and ESD transients protection.")
      (fields
        (field (name "INTERNAL_PART_NUMBER") "MCD-01207")
        (field (name "MANUFACTURER") "STMICROELECTRONICS")
        (field (name "PROVIDED_BY") "SUBCO with ST control")
      )
      (libsource (lib "MCD_PARTS_database") (part "ESD-TRANSIL"))
    )
    (comp (ref "U8")
      (value "ECMF02-2AMX6")
      (footprint "MCD_PARTS:ESD_QFN-6L_1P7X1P5_P050")
      (description "Common mode filter with ESD protection for USB 2.0 interface")
      (fields (field (name "INTERNAL_PART_NUMBER") "MCD-00649") (field (name "BMS_PART_NUMBER") "9151138"))
      (libsource (lib "MCD_PARTS_database") (part "ECMF02-2AMX6"))
    )
    (comp (ref "U9")
      (value "74AVC4TD245BQ")
      (footprint "MCD_PARTS:ICC_DHVQFN16-EPAD_SOT763-1_2P5X3P5_H0P85_P050")
      (description "4-bit dual supply translating transceiver with configurable voltage translation; 3-state")
      (fields
        (field (name "INTERNAL_PART_NUMBER") "MCD-01945")
        (field (name "MANUFACTURER_PART_NUMBER") "74AVC4TD245BQ,115")
      )
      (libsource (lib "MCD_PARTS_database") (part "74AVC4TD245BQ"))
    )
    (comp (ref "U10")
      (value "TPS259535DSG")
      (footprint "ICC_WSON8-EPAD_2X2_P050")
      (description "IC, 2V7 to 18V, 4A, 34mR, eFuse with fast overvoltage protection")
      (fields
        (field (name "INTERNAL_PART_NUMBER") "MCD-02532")
        (field (name "MANUFACTURER") "TEXAS INSTRUMENTS")
      )
      (libsource (lib "MCD_PARTS_database") (part "TPS259535DSG"))
    )
    (comp (ref "U11")
      (value "ST730M33R")
      (footprint "MCD_PARTS:ICC_SOT23-5L_H1P45")
      (description "LDO, 3.3V, 300mA, High input voltage: 2.5V to 28V, SOT23-5L")
      (fields
        (field (name "INTERNAL_PART_NUMBER") "MCD-02514")
        (field (name "MANUFACTURER") "STMICROELECTRONICS")
      )
      (libsource (lib "MCD_PARTS_database") (part "ST730M33R"))
    )
    (comp (ref "U12")
      (value "STMPS2151STR")
      (footprint "MCD_PARTS:MOS_SOT23-5L")
      (description "500mA, Enhanced single channel power switches with active high enable pin")
      (fields (field (name "INTERNAL_PART_NUMBER") "MCD-00159") (field (name "BMS_PART_NUMBER") "9159009"))
      (libsource (lib "MCD_PARTS_database") (part "STMPS2151STR"))
    )
    (comp (ref "U15")
      (value "74AVC4TD245BQ")
      (footprint "MCD_PARTS:ICC_DHVQFN16-EPAD_SOT763-1_2P5X3P5_H0P85_P050")
      (description "4-bit dual supply translating transceiver with configurable voltage translation; 3-state")
      (fields
        (field (name "INTERNAL_PART_NUMBER") "MCD-01945")
        (field (name "MANUFACTURER_PART_NUMBER") "74AVC4TD245BQ,115")
      )
      (libsource (lib "MCD_PARTS_database") (part "74AVC4TD245BQ"))
    )
    (comp (ref "X1")
      (value "24MHz")
      (footprint "MCD_PARTS:CRY_NX2016SA_4P")
      (description "Crystal, 24MHz, 6pF, +/-20ppm, 80R, 2x1.6mm")
      (fields (field (name "INTERNAL_PART_NUMBER") "MCD-01036") (field (name "BMS_PART_NUMBER") "9157045"))
      (libsource (lib "MCD_PARTS_database") (part "XTAL_4_PINS"))
    )
  )
  (nets
    (net (code "1") (name "/DBG_BOOTLOADER") (class "Default")
      (node (ref "R60") (pin "1") (pinfunction "1_1") (pintype "passive"))
      (node (ref "U6") (pin "14") (pinfunction "B1_14") (pintype "passive"))
    )
    (net (code "2") (name "/HiZ_DBG_IF_EN") (class "Default")
      (node (ref "JP4") (pin "2") (pinfunction "NO_2") (pintype "passive"))
      (node (ref "R47") (pin "2") (pinfunction "2_2") (pintype "passive"))
      (node (ref "U9") (pin "9") (pinfunction "~{OE}_9") (pintype "passive"))
    )
    (net (code "3") (name "/JTCK{slash}SWCLK") (class "Default")
      (node (ref "R34") (pin "2") (pinfunction "2_2") (pintype "passive"))
      (node (ref "U6") (pin "11") (pinfunction "B4_11") (pintype "passive"))
    )
    (net (code "4") (name "/JTDI") (class "Default")
      (node (ref "R37") (pin "2") (pinfunction "2_2") (pintype "passive"))
    )
    (net (code "5") (name "/JTDO{slash}SWO") (class "Default")
      (node (ref "R18") (pin "1") (pinfunction "1_1") (pintype "passive"))
      (node (ref "U6") (pin "13") (pinfunction "B2_13") (pintype "passive"))
    )
    (net (code "6") (name "/JTMS{slash}SWDIO") (class "Default")
      (node (ref "R35") (pin "2") (pinfunction "2_2") (pintype "passive"))
    )
    (net (code "7") (name "/NRST") (class "Default")
      (node (ref "R29") (pin "2") (pinfunction "2_2") (pintype "passive"))
    )
    (net (code "8") (name "/STLK_LED") (class "Default")
      (node (ref "U5") (pin "D15") (pinfunction "STLK_LED/PA10_D15") (pintype "passive"))
    )
    (net (code "9") (name "/STLK_OSC_IN") (class "Default")
      (node (ref "C28") (pin "2") (pinfunction "2_2") (pintype "passive"))
      (node (ref "U5") (pin "G1") (pinfunction "OSC_IN/PH0_G1") (pintype "passive"))
      (node (ref "X1") (pin "1") (pinfunction "1_1") (pintype "passive"))
    )
    (net (code "10") (name "/STLK_OSC_OUT") (class "Default")
      (node (ref "C29") (pin "1") (pinfunction "1_1") (pintype "passive"))
      (node (ref "U5") (pin "H1") (pinfunction "OSC_OUT/PH1_H1") (pintype "passive"))
      (node (ref "X1") (pin "3") (pinfunction "3_3") (pintype "passive"))
    )
    (net (code "11") (name "/STLK_SWCLK") (class "Default")
      (node (ref "CN16") (pin "2") (pinfunction "2_2") (pintype "passive"))
      (node (ref "U5") (pin "A14") (pinfunction "STLK_SWCLK/PA14_A14") (pintype "passive"))
    )
    (net (code "12") (name "/STLK_SWDIO") (class "Default")
      (node (ref "CN16") (pin "4") (pinfunction "4_4") (pintype "passive"))
      (node (ref "U5") (pin "A15") (pinfunction "STLK_SWDIO/PA13_A15") (pintype "passive"))
    )
    (net (code "13") (name "/STLK_UCPD_CC1_C") (class "Default")
      (node (ref "C26") (pin "1") (pinfunction "1_1") (pintype "passive"))
      (node (ref "R20") (pin "2") (pinfunction "2_2") (pintype "passive"))
      (node (ref "U5") (pin "M5") (pinfunction "ADCx_IN13/PC3_M5") (pintype "passive"))
    )
    (net (code "14") (name "/STLK_UCPD_CC2_C") (class "Default")
      (node (ref "C27") (pin "1") (pinfunction "1_1") (pintype "passive"))
      (node (ref "R22") (pin "2") (pinfunction "2_2") (pintype "passive"))
      (node (ref "U5") (pin "N5") (pinfunction "ADCx_IN14/PC4_N5") (pintype "passive"))
    )
    (net (code "15") (name "/STLK_USB_CN_N") (class "Default")
      (node (ref "CN15") (pin "A7") (pinfunction "D-1_A7") (pintype "passive"))
      (node (ref "CN15") (pin "B7") (pinfunction "D-2_B7") (pintype "passive"))
      (node (ref "U8") (pin "2") (pinfunction "D-_2") (pintype "passive"))
    )
    (net (code "16") (name "/STLK_USB_CN_P") (class "Default")
      (node (ref "CN15") (pin "A6") (pinfunction "D+1_A6") (pintype "passive"))
      (node (ref "CN15") (pin "B6") (pinfunction "D+2_B6") (pintype "passive"))
      (node (ref "U8") (pin "1") (pinfunction "D+_1") (pintype "passive"))
    )
    (net (code "17") (name "/STLK_USB_N") (class "Default")
      (node (ref "U5") (pin "R14") (pinfunction "USB_DEV_HS_N/PB14_R14") (pintype "passive"))
      (node (ref "U8") (pin "5") (pinfunction "D-_5") (pintype "passive"))
    )
    (net (code "18") (name "/STLK_USB_P") (class "Default")
      (node (ref "U5") (pin "R15") (pinfunction "USB_DEV_HS_P/PB15_R15") (pintype "passive"))
      (node (ref "U8") (pin "6") (pinfunction "D+_6") (pintype "passive"))
    )
    (net (code "19") (name "/STLK_VCP_RX") (class "Default")
      (node (ref "R55") (pin "1") (pinfunction "1_1") (pintype "passive"))
      (node (ref "U5") (pin "C10") (pinfunction "STLK_VCP_RX/PG9_C10") (pintype "passive"))
    )
    (net (code "20") (name "/STLK_VCP_TX") (class "Default")
      (node (ref "R56") (pin "1") (pinfunction "1_1") (pintype "passive"))
      (node (ref "U5") (pin "A7") (pinfunction "STLK_VCP_TX/PG14_A7") (pintype "passive"))
    )
    (net (code "21") (name "/SW_DIR") (class "Default")
      (node (ref "R41") (pin "2") (pinfunction "2_2") (pintype "passive"))
      (node (ref "U5") (pin "R3") (pinfunction "T_SW_DIR/PA7_R3") (pintype "passive"))
      (node (ref "U9") (pin "10") (pinfunction "DIR3_10") (pintype "passive"))
    )
    (net (code "22") (name "/T_DBG_BOOT") (class "Default")
      (node (ref "R59") (pin "2") (pinfunction "2_2") (pintype "passive"))
      (node (ref "U5") (pin "B3") (pinfunction "GPIO3/PE6_B3") (pintype "passive"))
      (node (ref "U6") (pin "3") (pinfunction "A1_3") (pintype "passive"))
    )
    (net (code "23") (name "/T_DBG_RST") (class "Default")
      (node (ref "R2") (pin "2") (pinfunction "2_2") (pintype "passive"))
      (node (ref "U5") (pin "B2") (pinfunction "GPIO2/PE5_B2") (pintype "passive"))
    )
    (net (code "24") (name "/T_JRCLK") (class "Default")
      (node (ref "R17") (pin "1") (pinfunction "1_1") (pintype "passive"))
      (node (ref "U5") (pin "A10") (pinfunction "T_JRCLK/PB3_A10") (pintype "passive"))
      (node (ref "U6") (pin "6") (pinfunction "A4_6") (pintype "passive"))
    )
    (net (code "25") (name "/T_JTDI") (class "Default")
      (node (ref "R27") (pin "1") (pinfunction "1_1") (pintype "passive"))
      (node (ref "U5") (pin "L3") (pinfunction "T_JTDI/PF8_L3") (pintype "passive"))
      (node (ref "U9") (pin "6") (pinfunction "A4_6") (pintype "passive"))
    )
    (net (code "26") (name "/T_MCO") (class "Default")
      (node (ref "R21") (pin "1") (pinfunction "1_1") (pintype "passive"))
      (node (ref "U5") (pin "F15") (pinfunction "T_MCO/PA8_F15") (pintype "passive"))
    )
    (net (code "27") (name "/T_PWR_EN") (class "Default")
      (node (ref "R46") (pin "2") (pinfunction "2_2") (pintype "passive"))
      (node (ref "R53") (pin "2") (pinfunction "2_2") (pintype "passive"))
      (node (ref "U10") (pin "2") (pinfunction "EN/UVLO_2") (pintype "passive"))
      (node (ref "U12") (pin "4") (pinfunction "EN_4") (pintype "passive"))
      (node (ref "U5") (pin "R5") (pinfunction "T_PWR_EN/PB0_R5") (pintype "passive"))
    )
    (net (code "28") (name "/T_PWR_EXT") (class "Default")
      (node (ref "R36") (pin "1") (pinfunction "1_1") (pintype "passive"))
      (node (ref "R38") (pin "1") (pinfunction "1_1") (pintype "passive"))
      (node (ref "U5") (pin "R4") (pinfunction "T_PWR_EXT/PB1_R4") (pintype "passive"))
    )
    (net (code "29") (name "/T_PWR_INT") (class "Default")
      (node (ref "R40") (pin "2") (pinfunction "2_2") (pintype "passive"))
      (node (ref "R42") (pin "2") (pinfunction "2_2") (pintype "passive"))
      (node (ref "R52") (pin "2") (pinfunction "2_2") (pintype "passive"))
      (node (ref "U12") (pin "3") (pinfunction "~{FAULT}_3") (pintype "passive"))
      (node (ref "U5") (pin "B13") (pinfunction "T_PWR_INT/PC11_B13") (pintype "passive"))
    )
    (net (code "30") (name "/T_PWR_LED") (class "Default")
      (node (ref "U5") (pin "H15") (pinfunction "T_PWR_LED/PC6_H15") (pintype "passive"))
    )
    (net (code "31") (name "/T_PWR_SEL1") (class "Default")
      (node (ref "R43") (pin "2") (pinfunction "2_2") (pintype "passive"))
      (node (ref "U5") (pin "D10") (pinfunction "T_PWR_SEL1/PD4_D10") (pintype "passive"))
    )
    (net (code "32") (name "/T_PWR_SEL2") (class "Default")
      (node (ref "R44") (pin "2") (pinfunction "2_2") (pintype "passive"))
      (node (ref "U5") (pin "C11") (pinfunction "T_PWR_SEL2/PD5_C11") (pintype "passive"))
    )
    (net (code "33") (name "/T_SWCLK") (class "Default")
      (node (ref "R25") (pin "1") (pinfunction "1_1") (pintype "passive"))
      (node (ref "U5") (pin "M11") (pinfunction "T_SWCLK/PH6_M11") (pintype "passive"))
      (node (ref "U5") (pin "M6") (pinfunction "T_JCLK_OUT/PB2_M6") (pintype "passive"))
      (node (ref "U9") (pin "4") (pinfunction "A2_4") (pintype "passive"))
    )
    (net (code "34") (name "/T_SWDIO") (class "Default")
      (node (ref "R26") (pin "1") (pinfunction "1_1") (pintype "passive"))
      (node (ref "U5") (pin "L2") (pinfunction "T_JTMS/T_SWDIO_OUT/PF9_L2") (pintype "passive"))
      (node (ref "U5") (pin "N12") (pinfunction "T_SWDIO_IN/PH7_N12") (pintype "passive"))
      (node (ref "U9") (pin "5") (pinfunction "A3_5") (pintype "passive"))
    )
    (net (code "35") (name "/T_SWO") (class "Default")
      (node (ref "R15") (pin "1") (pinfunction "1_1") (pintype "passive"))
      (node (ref "U5") (pin "A6") (pinfunction "T_JTDO/PB5_A6") (pintype "passive"))
      (node (ref "U5") (pin "D12") (pinfunction "T_SWO/PD2_D12") (pintype "passive"))
      (node (ref "U6") (pin "4") (pinfunction "A2_4") (pintype "passive"))
    )
    (net (code "36") (name "/T_VCC_AIN") (class "Default")
      (node (ref "R31") (pin "1") (pinfunction "1_1") (pintype "passive"))
      (node (ref "R33") (pin "1") (pinfunction "1_1") (pintype "passive"))
      (node (ref "U5") (pin "N3") (pinfunction "T_VCC_AIN/PA0_N3") (pintype "passive"))
    )
    (net (code "37") (name "/T_VCP1_RX") (class "Default")
      (node (ref "R16") (pin "1") (pinfunction "1_1") (pintype "passive"))
      (node (ref "R55") (pin "2") (pinfunction "2_2") (pintype "passive"))
      (node (ref "U6") (pin "5") (pinfunction "A3_5") (pintype "passive"))
    )
    (net (code "38") (name "/T_VCP1_TX") (class "Default")
      (node (ref "R24") (pin "2") (pinfunction "2_2") (pintype "passive"))
      (node (ref "R56") (pin "2") (pinfunction "2_2") (pintype "passive"))
      (node (ref "U9") (pin "3") (pinfunction "A1_3") (pintype "passive"))
    )
    (net (code "39") (name "/T_VCP2_CTS") (class "Default")
      (node (ref "R63") (pin "1") (pinfunction "1_1") (pintype "passive"))
      (node (ref "U15") (pin "5") (pinfunction "A3_5") (pintype "passive"))
      (node (ref "U5") (pin "N14") (pinfunction "UART_CTS/PD11_N14") (pintype "passive"))
    )
    (net (code "40") (name "/T_VCP2_RTS") (class "Default")
      (node (ref "R64") (pin "1") (pinfunction "1_1") (pintype "passive"))
      (node (ref "U15") (pin "6") (pinfunction "A4_6") (pintype "passive"))
      (node (ref "U5") (pin "N13") (pinfunction "UART_RTS/PD12_N13") (pintype "passive"))
    )
    (net (code "41") (name "/T_VCP2_RX") (class "Default")
      (node (ref "R57") (pin "2") (pinfunction "2_2") (pintype "passive"))
      (node (ref "R62") (pin "1") (pinfunction "1_1") (pintype "passive"))
      (node (ref "U15") (pin "4") (pinfunction "A2_4") (pintype "passive"))
    )
    (net (code "42") (name "/T_VCP2_TX") (class "Default")
      (node (ref "R58") (pin "2") (pinfunction "2_2") (pintype "passive"))
      (node (ref "R61") (pin "1") (pinfunction "1_1") (pintype "passive"))
      (node (ref "U15") (pin "3") (pinfunction "A1_3") (pintype "passive"))
    )
    (net (code "43") (name "/VCP1_T_RX") (class "Default")
      (node (ref "R32") (pin "2") (pinfunction "2_2") (pintype "passive"))
    )
    (net (code "44") (name "/VCP1_T_TX") (class "Default")
      (node (ref "R19") (pin "1") (pinfunction "1_1") (pintype "passive"))
      (node (ref "U6") (pin "12") (pinfunction "B3_12") (pintype "passive"))
    )
    (net (code "45") (name "/VCP2_T_CTS") (class "Default")
      (node (ref "R67") (pin "1") (pinfunction "1_1") (pintype "passive"))
      (node (ref "U15") (pin "11") (pinfunction "B4_11") (pintype "passive"))
    )
    (net (code "46") (name "/VCP2_T_RTS") (class "Default")
      (node (ref "R66") (pin "1") (pinfunction "1_1") (pintype "passive"))
      (node (ref "U15") (pin "12") (pinfunction "B3_12") (pintype "passive"))
    )
    (net (code "47") (name "/VCP2_T_RX") (class "Default")
      (node (ref "U15") (pin "14") (pinfunction "B1_14") (pintype "passive"))
    )
    (net (code "48") (name "/VCP2_T_TX") (class "Default")
      (node (ref "R65") (pin "1") (pinfunction "1_1") (pintype "passive"))
      (node (ref "U15") (pin "13") (pinfunction "B2_13") (pintype "passive"))
    )
    (net (code "49") (name "3V3_STLK") (class "Default")
      (node (ref "C24") (pin "2") (pinfunction "2_2") (pintype "passive"))
      (node (ref "C30") (pin "2") (pinfunction "2_2") (pintype "passive"))
      (node (ref "C37") (pin "1") (pinfunction "1_1") (pintype "passive"))
      (node (ref "C38") (pin "1") (pinfunction "1_1") (pintype "passive"))
      (node (ref "C39") (pin "1") (pinfunction "1_1") (pintype "passive"))
      (node (ref "C40") (pin "1") (pinfunction "1_1") (pintype "passive"))
      (node (ref "C41") (pin "1") (pinfunction "1_1") (pintype "passive"))
      (node (ref "C42") (pin "1") (pinfunction "1_1") (pintype "passive"))
      (node (ref "C43") (pin "1") (pinfunction "1_1") (pintype "passive"))
      (node (ref "C44") (pin "1") (pinfunction "1_1") (pintype "passive"))
      (node (ref "C45") (pin "1") (pinfunction "1_1") (pintype "passive"))
      (node (ref "C46") (pin "1") (pinfunction "1_1") (pintype "passive"))
      (node (ref "C47") (pin "1") (pinfunction "1_1") (pintype "passive"))
      (node (ref "C48") (pin "1") (pinfunction "1_1") (pintype "passive"))
      (node (ref "C49") (pin "1") (pinfunction "1_1") (pintype "passive"))
      (node (ref "C50") (pin "1") (pinfunction "1_1") (pintype "passive"))
      (node (ref "C51") (pin "1") (pinfunction "1_1") (pintype "passive"))
      (node (ref "C52") (pin "1") (pinfunction "1_1") (pintype "passive"))
      (node (ref "C53") (pin "1") (pinfunction "1_1") (pintype "passive"))
      (node (ref "C55") (pin "2") (pinfunction "2_2") (pintype "passive"))
      (node (ref "C60") (pin "2") (pinfunction "2_2") (pintype "passive"))
      (node (ref "CN16") (pin "1") (pinfunction "1_1") (pintype "passive"))
      (node (ref "JP4") (pin "1") (pinfunction "COMMON_1") (pintype "passive"))
      (node (ref "R15") (pin "2") (pinfunction "2_2") (pintype "passive"))
      (node (ref "R16") (pin "2") (pinfunction "2_2") (pintype "passive"))
      (node (ref "R17") (pin "2") (pinfunction "2_2") (pintype "passive"))
      (node (ref "R2") (pin "1") (pinfunction "1_1") (pintype "passive"))
      (node (ref "R24") (pin "1") (pinfunction "1_1") (pintype "passive"))
      (node (ref "R25") (pin "2") (pinfunction "2_2") (pintype "passive"))
      (node (ref "R26") (pin "2") (pinfunction "2_2") (pintype "passive"))
      (node (ref "R27") (pin "2") (pinfunction "2_2") (pintype "passive"))
      (node (ref "R39") (pin "2") (pinfunction "2_2") (pintype "passive"))
      (node (ref "R52") (pin "1") (pinfunction "1_1") (pintype "passive"))
      (node (ref "R61") (pin "2") (pinfunction "2_2") (pintype "passive"))
      (node (ref "R62") (pin "2") (pinfunction "2_2") (pintype "passive"))
      (node (ref "R63") (pin "2") (pinfunction "2_2") (pintype "passive"))
      (node (ref "R64") (pin "2") (pinfunction "2_2") (pintype "passive"))
      (node (ref "U11") (pin "1") (pinfunction "VOUT_1") (pintype "passive"))
      (node (ref "U15") (pin "1") (pinfunction "VCCA_1") (pintype "passive"))
      (node (ref "U15") (pin "2") (pinfunction "DIR1_2") (pintype "passive"))
      (node (ref "U15") (pin "7") (pinfunction "DIR4_7") (pintype "passive"))
      (node (ref "U5") (pin "C1") (pinfunction "VBAT_C1") (pintype "passive"))
      (node (ref "U5") (pin "C5") (pinfunction "VDD_C5") (pintype "passive"))
      (node (ref "U5") (pin "C6") (pinfunction "PDR_ON_C6") (pintype "passive"))
      (node (ref "U5") (pin "C7") (pinfunction "VDD_C7") (pintype "passive"))
      (node (ref "U5") (pin "C8") (pinfunction "VDD_C8") (pintype "passive"))
      (node (ref "U5") (pin "C9") (pinfunction "VDD_C9") (pintype "passive"))
      (node (ref "U5") (pin "F3") (pinfunction "VDD_F3") (pintype "passive"))
      (node (ref "U5") (pin "G13") (pinfunction "VDD_G13") (pintype "passive"))
      (node (ref "U5") (pin "G3") (pinfunction "VDD_G3") (pintype "passive"))
      (node (ref "U5") (pin "H13") (pinfunction "VDD_H13") (pintype "passive"))
      (node (ref "U5") (pin "J12") (pinfunction "VDD_J12") (pintype "passive"))
      (node (ref "U5") (pin "J13") (pinfunction "VDD_J13") (pintype "passive"))
      (node (ref "U5") (pin "K4") (pinfunction "VDD_K4") (pintype "passive"))
      (node (ref "U5") (pin "N10") (pinfunction "VDD_N10") (pintype "passive"))
      (node (ref "U5") (pin "N8") (pinfunction "VDD_N8") (pintype "passive"))
      (node (ref "U5") (pin "N9") (pinfunction "VDD_N9") (pintype "passive"))
      (node (ref "U5") (pin "P1") (pinfunction "VREF+_P1") (pintype "passive"))
      (node (ref "U5") (pin "R1") (pinfunction "VDDA_R1") (pintype "passive"))
      (node (ref "U6") (pin "1") (pinfunction "VCCA_1") (pintype "passive"))
      (node (ref "U6") (pin "2") (pinfunction "DIR1_2") (pintype "passive"))
      (node (ref "U9") (pin "1") (pinfunction "VCCA_1") (pintype "passive"))
      (node (ref "U9") (pin "15") (pinfunction "DIR2_15") (pintype "passive"))
      (node (ref "U9") (pin "2") (pinfunction "DIR1_2") (pintype "passive"))
      (node (ref "U9") (pin "7") (pinfunction "DIR4_7") (pintype "passive"))
    )
    (net (code "50") (name "5V") (class "Default")
      (node (ref "R36") (pin "2") (pinfunction "2_2") (pintype "passive"))
    )
    (net (code "51") (name "5V_STLK") (class "Default")
      (node (ref "C34") (pin "2") (pinfunction "2_2") (pintype "passive"))
      (node (ref "C59") (pin "2") (pinfunction "2_2") (pintype "passive"))
      (node (ref "R40") (pin "1") (pinfunction "1_1") (pintype "passive"))
      (node (ref "U10") (pin "5") (pinfunction "OUT_5") (pintype "passive"))
      (node (ref "U10") (pin "6") (pinfunction "QOD_6") (pintype "passive"))
      (node (ref "U12") (pin "1") (pinfunction "OUT_1") (pintype "passive"))
    )
    (net (code "52") (name "GND") (class "Default")
      (node (ref "C23") (pin "2") (pinfunction "2_2") (pintype "passive"))
      (node (ref "C24") (pin "1") (pinfunction "1_1") (pintype "passive"))
      (node (ref "C25") (pin "2") (pinfunction "2_2") (pintype "passive"))
      (node (ref "C26") (pin "2") (pinfunction "2_2") (pintype "passive"))
      (node (ref "C27") (pin "2") (pinfunction "2_2") (pintype "passive"))
      (node (ref "C28") (pin "1") (pinfunction "1_1") (pintype "passive"))
      (node (ref "C29") (pin "2") (pinfunction "2_2") (pintype "passive"))
      (node (ref "C30") (pin "1") (pinfunction "1_1") (pintype "passive"))
      (node (ref "C31") (pin "2") (pinfunction "2_2") (pintype "passive"))
      (node (ref "C32") (pin "1") (pinfunction "1_1") (pintype "passive"))
      (node (ref "C33") (pin "1") (pinfunction "1_1") (pintype "passive"))
      (node (ref "C34") (pin "1") (pinfunction "1_1") (pintype "passive"))
      (node (ref "C35") (pin "1") (pinfunction "1_1") (pintype "passive"))
      (node (ref "C36") (pin "1") (pinfunction "1_1") (pintype "passive"))
      (node (ref "C37") (pin "2") (pinfunction "2_2") (pintype "passive"))
      (node (ref "C38") (pin "2") (pinfunction "2_2") (pintype "passive"))
      (node (ref "C39") (pin "2") (pinfunction "2_2") (pintype "passive"))
      (node (ref "C40") (pin "2") (pinfunction "2_2") (pintype "passive"))
      (node (ref "C41") (pin "2") (pinfunction "2_2") (pintype "passive"))
      (node (ref "C42") (pin "2") (pinfunction "2_2") (pintype "passive"))
      (node (ref "C43") (pin "2") (pinfunction "2_2") (pintype "passive"))
      (node (ref "C44") (pin "2") (pinfunction "2_2") (pintype "passive"))
      (node (ref "C45") (pin "2") (pinfunction "2_2") (pintype "passive"))
      (node (ref "C46") (pin "2") (pinfunction "2_2") (pintype "passive"))
      (node (ref "C47") (pin "2") (pinfunction "2_2") (pintype "passive"))
      (node (ref "C48") (pin "2") (pinfunction "2_2") (pintype "passive"))
      (node (ref "C49") (pin "2") (pinfunction "2_2") (pintype "passive"))
      (node (ref "C50") (pin "2") (pinfunction "2_2") (pintype "passive"))
      (node (ref "C51") (pin "2") (pinfunction "2_2") (pintype "passive"))
      (node (ref "C52") (pin "2") (pinfunction "2_2") (pintype "passive"))
      (node (ref "C53") (pin "2") (pinfunction "2_2") (pintype "passive"))
      (node (ref "C54") (pin "1") (pinfunction "1_1") (pintype "passive"))
      (node (ref "C55") (pin "1") (pinfunction "1_1") (pintype "passive"))
      (node (ref "C56") (pin "1") (pinfunction "1_1") (pintype "passive"))
      (node (ref "C57") (pin "1") (pinfunction "1_1") (pintype "passive"))
      (node (ref "C58") (pin "1") (pinfunction "1_1") (pintype "passive"))
      (node (ref "C59") (pin "1") (pinfunction "1_1") (pintype "passive"))
      (node (ref "C60") (pin "1") (pinfunction "1_1") (pintype "passive"))
      (node (ref "C61") (pin "2") (pinfunction "2_2") (pintype "passive"))
      (node (ref "CN15") (pin "A1") (pinfunction "GND1_A1") (pintype "passive"))
      (node (ref "CN15") (pin "A12") (pinfunction "GND2_A12") (pintype "passive"))
      (node (ref "CN15") (pin "B1") (pinfunction "GND3_B1") (pintype "passive"))
      (node (ref "CN15") (pin "B12") (pinfunction "GND4_B12") (pintype "passive"))
      (node (ref "CN15") (pin "SH1") (pinfunction "Shield1_SH1") (pintype "passive"))
      (node (ref "CN15") (pin "SH2") (pinfunction "Shield2_SH2") (pintype "passive"))
      (node (ref "CN15") (pin "SH3") (pinfunction "Shield3_SH3") (pintype "passive"))
      (node (ref "CN15") (pin "SH4") (pinfunction "Shield4_SH4") (pintype "passive"))
      (node (ref "CN16") (pin "3") (pinfunction "3_3") (pintype "passive"))
      (node (ref "JP3") (pin "2") (pinfunction "NO_2") (pintype "passive"))
      (node (ref "R14") (pin "2") (pinfunction "2_2") (pintype "passive"))
      (node (ref "R23") (pin "2") (pinfunction "2_2") (pintype "passive"))
      (node (ref "R30") (pin "2") (pinfunction "2_2") (pintype "passive"))
      (node (ref "R31") (pin "2") (pinfunction "2_2") (pintype "passive"))
      (node (ref "R38") (pin "2") (pinfunction "2_2") (pintype "passive"))
      (node (ref "R41") (pin "1") (pinfunction "1_1") (pintype "passive"))
      (node (ref "R42") (pin "1") (pinfunction "1_1") (pintype "passive"))
      (node (ref "R45") (pin "2") (pinfunction "2_2") (pintype "passive"))
      (node (ref "R46") (pin "1") (pinfunction "1_1") (pintype "passive"))
      (node (ref "R47") (pin "1") (pinfunction "1_1") (pintype "passive"))
      (node (ref "R53") (pin "1") (pinfunction "1_1") (pintype "passive"))
      (node (ref "R59") (pin "1") (pinfunction "1_1") (pintype "passive"))
      (node (ref "U10") (pin "8") (pinfunction "GND_8") (pintype "passive"))
      (node (ref "U10") (pin "9") (pinfunction "EP_9") (pintype "passive"))
      (node (ref "U11") (pin "2") (pinfunction "GND_2") (pintype "passive"))
      (node (ref "U12") (pin "2") (pinfunction "GND_2") (pintype "passive"))
      (node (ref "U15") (pin "10") (pinfunction "DIR3_10") (pintype "passive"))
      (node (ref "U15") (pin "15") (pinfunction "DIR2_15") (pintype "passive"))
      (node (ref "U15") (pin "17") (pinfunction "EP_17") (pintype "passive"))
      (node (ref "U15") (pin "8") (pinfunction "GND_8") (pintype "passive"))
      (node (ref "U15") (pin "9") (pinfunction "~{OE}_9") (pintype "passive"))
      (node (ref "U5") (pin "D5") (pinfunction "VSS_D5") (pintype "passive"))
      (node (ref "U5") (pin "D6") (pinfunction "BOOT0_D6") (pintype "passive"))
      (node (ref "U5") (pin "D7") (pinfunction "VSS_D7") (pintype "passive"))
      (node (ref "U5") (pin "D8") (pinfunction "VSS_D8") (pintype "passive"))
      (node (ref "U5") (pin "D9") (pinfunction "VSS_D9") (pintype "passive"))
      (node (ref "U5") (pin "F10") (pinfunction "VSS_F10") (pintype "passive"))
      (node (ref "U5") (pin "F12") (pinfunction "VSS_F12") (pintype "passive"))
      (node (ref "U5") (pin "F2") (pinfunction "VSS_F2") (pintype "passive"))
      (node (ref "U5") (pin "F6") (pinfunction "VSS_F6") (pintype "passive"))
      (node (ref "U5") (pin "F7") (pinfunction "VSS_F7") (pintype "passive"))
      (node (ref "U5") (pin "F8") (pinfunction "VSS_F8") (pintype "passive"))
      (node (ref "U5") (pin "F9") (pinfunction "VSS_F9") (pintype "passive"))
      (node (ref "U5") (pin "G10") (pinfunction "VSS_G10") (pintype "passive"))
      (node (ref "U5") (pin "G12") (pinfunction "VSS_G12") (pintype "passive"))
      (node (ref "U5") (pin "G2") (pinfunction "VSS_G2") (pintype "passive"))
      (node (ref "U5") (pin "G6") (pinfunction "VSS_G6") (pintype "passive"))
      (node (ref "U5") (pin "G7") (pinfunction "VSS_G7") (pintype "passive"))
      (node (ref "U5") (pin "G8") (pinfunction "VSS_G8") (pintype "passive"))
      (node (ref "U5") (pin "G9") (pinfunction "VSS_G9") (pintype "passive"))
      (node (ref "U5") (pin "H10") (pinfunction "VSS_H10") (pintype "passive"))
      (node (ref "U5") (pin "H12") (pinfunction "VSS_H12") (pintype "passive"))
      (node (ref "U5") (pin "H6") (pinfunction "VSS_H6") (pintype "passive"))
      (node (ref "U5") (pin "H7") (pinfunction "VSS_H7") (pintype "passive"))
      (node (ref "U5") (pin "H8") (pinfunction "VSS_H8") (pintype "passive"))
      (node (ref "U5") (pin "H9") (pinfunction "VSS_H9") (pintype "passive"))
      (node (ref "U5") (pin "J10") (pinfunction "VSS_J10") (pintype "passive"))
      (node (ref "U5") (pin "J6") (pinfunction "VSS_J6") (pintype "passive"))
      (node (ref "U5") (pin "J7") (pinfunction "VSS_J7") (pintype "passive"))
      (node (ref "U5") (pin "J8") (pinfunction "VSS_J8") (pintype "passive"))
      (node (ref "U5") (pin "J9") (pinfunction "VSS_J9") (pintype "passive"))
      (node (ref "U5") (pin "K10") (pinfunction "VSS_K10") (pintype "passive"))
      (node (ref "U5") (pin "K6") (pinfunction "VSS_K6") (pintype "passive"))
      (node (ref "U5") (pin "K7") (pinfunction "VSS_K7") (pintype "passive"))
      (node (ref "U5") (pin "K8") (pinfunction "VSS_K8") (pintype "passive"))
      (node (ref "U5") (pin "K9") (pinfunction "VSS_K9") (pintype "passive"))
      (node (ref "U5") (pin "L4") (pinfunction "BYPASS-REG_L4") (pintype "passive"))
      (node (ref "U5") (pin "M1") (pinfunction "VSSA_M1") (pintype "passive"))
      (node (ref "U5") (pin "M8") (pinfunction "VSS_M8") (pintype "passive"))
      (node (ref "U5") (pin "M9") (pinfunction "VSS_M9") (pintype "passive"))
      (node (ref "U5") (pin "N1") (pinfunction "VREF-_N1") (pintype "passive"))
      (node (ref "U6") (pin "10") (pinfunction "DIR3_10") (pintype "passive"))
      (node (ref "U6") (pin "15") (pinfunction "DIR2_15") (pintype "passive"))
      (node (ref "U6") (pin "17") (pinfunction "EP_17") (pintype "passive"))
      (node (ref "U6") (pin "7") (pinfunction "DIR4_7") (pintype "passive"))
      (node (ref "U6") (pin "8") (pinfunction "GND_8") (pintype "passive"))
      (node (ref "U6") (pin "9") (pinfunction "~{OE}_9") (pintype "passive"))
      (node (ref "U7") (pin "2") (pinfunction "GND_2") (pintype "passive"))
      (node (ref "U8") (pin "3") (pinfunction "GND_3") (pintype "passive"))
      (node (ref "U9") (pin "17") (pinfunction "EP_17") (pintype "passive"))
      (node (ref "U9") (pin "8") (pinfunction "GND_8") (pintype "passive"))
      (node (ref "X1") (pin "2") (pinfunction "2_2") (pintype "passive"))
      (node (ref "X1") (pin "4") (pinfunction "4_4") (pintype "passive"))
    )
    (net (code "53") (name "Net-(CN15-CC1)") (class "Default")
      (node (ref "CN15") (pin "A5") (pinfunction "CC1_A5") (pintype "passive"))
      (node (ref "R14") (pin "1") (pinfunction "1_1") (pintype "passive"))
      (node (ref "R20") (pin "1") (pinfunction "1_1") (pintype "passive"))
    )
    (net (code "54") (name "Net-(CN15-CC2)") (class "Default")
      (node (ref "CN15") (pin "B5") (pinfunction "CC2_B5") (pintype "passive"))
      (node (ref "R22") (pin "1") (pinfunction "1_1") (pintype "passive"))
      (node (ref "R23") (pin "1") (pinfunction "1_1") (pintype "passive"))
    )
    (net (code "55") (name "Net-(D1-K)") (class "Default")
      (node (ref "C54") (pin "2") (pinfunction "2_2") (pintype "passive"))
      (node (ref "D1") (pin "2") (pinfunction "K_2") (pintype "passive"))
      (node (ref "U11") (pin "3") (pinfunction "VIN_3") (pintype "passive"))
      (node (ref "U11") (pin "5") (pinfunction "EN_5") (pintype "passive"))
    )
    (net (code "56") (name "Net-(JP3-COMMON)") (class "Default")
      (node (ref "C32") (pin "2") (pinfunction "2_2") (pintype "passive"))
      (node (ref "JP3") (pin "1") (pinfunction "COMMON_1") (pintype "passive"))
      (node (ref "U5") (pin "J1") (pinfunction "NRST_J1") (pintype "passive"))
    )
    (net (code "57") (name "Net-(R21-Pad2)") (class "Default")
      (node (ref "R21") (pin "2") (pinfunction "2_2") (pintype "passive"))
      (node (ref "TP1") (pin "1") (pinfunction "1_1") (pintype "passive"))
    )
    (net (code "58") (name "Net-(U5A-HW_TYP_0{slash}PI4)") (class "Default")
      (node (ref "R39") (pin "1") (pinfunction "1_1") (pintype "passive"))
      (node (ref "U5") (pin "D4") (pinfunction "HW_TYP_0/PI4_D4") (pintype "passive"))
    )
    (net (code "59") (name "Net-(U5A-REXT_OTGPHY)") (class "Default")
      (node (ref "R30") (pin "1") (pinfunction "1_1") (pintype "passive"))
      (node (ref "U5") (pin "J15") (pinfunction "REXT_OTGPHY_J15") (pintype "passive"))
    )
    (net (code "60") (name "Net-(U5A-T_NRST{slash}PA6)") (class "Default")
      (node (ref "R29") (pin "1") (pinfunction "1_1") (pintype "passive"))
      (node (ref "U5") (pin "P3") (pinfunction "T_NRST/PA6_P3") (pintype "passive"))
    )
    (net (code "61") (name "Net-(U5A-V12_OTGPHY)") (class "Default")
      (node (ref "C33") (pin "2") (pinfunction "2_2") (pintype "passive"))
      (node (ref "U5") (pin "J14") (pinfunction "V12_OTGPHY_J14") (pintype "passive"))
    )
    (net (code "62") (name "Net-(U5B-VCAP1)") (class "Default")
      (node (ref "C56") (pin "2") (pinfunction "2_2") (pintype "passive"))
      (node (ref "U5") (pin "M10") (pinfunction "VCAP1_M10") (pintype "passive"))
    )
    (net (code "63") (name "Net-(U5B-VCAP2)") (class "Default")
      (node (ref "C57") (pin "2") (pinfunction "2_2") (pintype "passive"))
      (node (ref "U5") (pin "F13") (pinfunction "VCAP2_F13") (pintype "passive"))
    )
    (net (code "64") (name "Net-(U5C-UART_RX{slash}PB11)") (class "Default")
      (node (ref "R57") (pin "1") (pinfunction "1_1") (pintype "passive"))
      (node (ref "U5") (pin "R13") (pinfunction "UART_RX/PB11_R13") (pintype "passive"))
    )
    (net (code "65") (name "Net-(U5C-UART_TX{slash}PC10)") (class "Default")
      (node (ref "R58") (pin "1") (pinfunction "1_1") (pintype "passive"))
      (node (ref "U5") (pin "B14") (pinfunction "UART_TX/PC10_B14") (pintype "passive"))
    )
    (net (code "66") (name "Net-(U9-B1)") (class "Default")
      (node (ref "R32") (pin "1") (pinfunction "1_1") (pintype "passive"))
      (node (ref "U9") (pin "14") (pinfunction "B1_14") (pintype "passive"))
    )
    (net (code "67") (name "Net-(U9-B2)") (class "Default")
      (node (ref "R34") (pin "1") (pinfunction "1_1") (pintype "passive"))
      (node (ref "U9") (pin "13") (pinfunction "B2_13") (pintype "passive"))
    )
    (net (code "68") (name "Net-(U9-B3)") (class "Default")
      (node (ref "R28") (pin "1") (pinfunction "1_1") (pintype "passive"))
      (node (ref "R35") (pin "1") (pinfunction "1_1") (pintype "passive"))
      (node (ref "U9") (pin "12") (pinfunction "B3_12") (pintype "passive"))
    )
    (net (code "69") (name "Net-(U9-B4)") (class "Default")
      (node (ref "R37") (pin "1") (pinfunction "1_1") (pintype "passive"))
      (node (ref "U9") (pin "11") (pinfunction "B4_11") (pintype "passive"))
    )
    (net (code "70") (name "Net-(U10-ILM)") (class "Default")
      (node (ref "R43") (pin "1") (pinfunction "1_1") (pintype "passive"))
      (node (ref "R44") (pin "1") (pinfunction "1_1") (pintype "passive"))
      (node (ref "R45") (pin "1") (pinfunction "1_1") (pintype "passive"))
      (node (ref "U10") (pin "7") (pinfunction "ILM_7") (pintype "passive"))
    )
    (net (code "71") (name "Net-(U10-dVdt)") (class "Default")
      (node (ref "C36") (pin "2") (pinfunction "2_2") (pintype "passive"))
      (node (ref "U10") (pin "1") (pinfunction "dVdt_1") (pintype "passive"))
    )
    (net (code "72") (name "VBUS_STLK") (class "Default")
      (node (ref "C23") (pin "1") (pinfunction "1_1") (pintype "passive"))
      (node (ref "C35") (pin "2") (pinfunction "2_2") (pintype "passive"))
      (node (ref "C58") (pin "2") (pinfunction "2_2") (pintype "passive"))
      (node (ref "CN15") (pin "A4") (pinfunction "VBUS1_A4") (pintype "passive"))
      (node (ref "CN15") (pin "A9") (pinfunction "VBUS2_A9") (pintype "passive"))
      (node (ref "CN15") (pin "B4") (pinfunction "VBUS3_B4") (pintype "passive"))
      (node (ref "CN15") (pin "B9") (pinfunction "VBUS4_B9") (pintype "passive"))
      (node (ref "D1") (pin "1") (pinfunction "A_1") (pintype "passive"))
      (node (ref "U10") (pin "3") (pinfunction "IN_3") (pintype "passive"))
      (node (ref "U10") (pin "4") (pinfunction "IN_4") (pintype "passive"))
      (node (ref "U12") (pin "5") (pinfunction "IN_5") (pintype "passive"))
      (node (ref "U7") (pin "1") (pinfunction "IO1_1") (pintype "passive"))
    )
    (net (code "73") (name "V_TARGET") (class "Default")
      (node (ref "C25") (pin "1") (pinfunction "1_1") (pintype "passive"))
      (node (ref "C31") (pin "1") (pinfunction "1_1") (pintype "passive"))
      (node (ref "C61") (pin "1") (pinfunction "1_1") (pintype "passive"))
      (node (ref "R18") (pin "2") (pinfunction "2_2") (pintype "passive"))
      (node (ref "R19") (pin "2") (pinfunction "2_2") (pintype "passive"))
      (node (ref "R28") (pin "2") (pinfunction "2_2") (pintype "passive"))
      (node (ref "R33") (pin "2") (pinfunction "2_2") (pintype "passive"))
      (node (ref "R60") (pin "2") (pinfunction "2_2") (pintype "passive"))
      (node (ref "R65") (pin "2") (pinfunction "2_2") (pintype "passive"))
      (node (ref "R66") (pin "2") (pinfunction "2_2") (pintype "passive"))
      (node (ref "R67") (pin "2") (pinfunction "2_2") (pintype "passive"))
      (node (ref "U15") (pin "16") (pinfunction "VCCB_16") (pintype "passive"))
      (node (ref "U6") (pin "16") (pinfunction "VCCB_16") (pintype "passive"))
      (node (ref "U9") (pin "16") (pinfunction "VCCB_16") (pintype "passive"))
    )
    (net (code "74") (name "unconnected-(CN15-RX1+-PadB11)") (class "Default")
      (node (ref "CN15") (pin "B11") (pinfunction "RX1+_B11") (pintype "passive+no_connect"))
    )
    (net (code "75") (name "unconnected-(CN15-RX1--PadB10)") (class "Default")
      (node (ref "CN15") (pin "B10") (pinfunction "RX1-_B10") (pintype "passive+no_connect"))
    )
    (net (code "76") (name "unconnected-(CN15-RX2+-PadA11)") (class "Default")
      (node (ref "CN15") (pin "A11") (pinfunction "RX2+_A11") (pintype "passive+no_connect"))
    )
    (net (code "77") (name "unconnected-(CN15-RX2--PadA10)") (class "Default")
      (node (ref "CN15") (pin "A10") (pinfunction "RX2-_A10") (pintype "passive+no_connect"))
    )
    (net (code "78") (name "unconnected-(CN15-SBU1-PadA8)") (class "Default")
      (node (ref "CN15") (pin "A8") (pinfunction "SBU1_A8") (pintype "passive+no_connect"))
    )
    (net (code "79") (name "unconnected-(CN15-SBU2-PadB8)") (class "Default")
      (node (ref "CN15") (pin "B8") (pinfunction "SBU2_B8") (pintype "passive+no_connect"))
    )
    (net (code "80") (name "unconnected-(CN15-TX1+-PadA2)") (class "Default")
      (node (ref "CN15") (pin "A2") (pinfunction "TX1+_A2") (pintype "passive+no_connect"))
    )
    (net (code "81") (name "unconnected-(CN15-TX1--PadA3)") (class "Default")
      (node (ref "CN15") (pin "A3") (pinfunction "TX1-_A3") (pintype "passive+no_connect"))
    )
    (net (code "82") (name "unconnected-(CN15-TX2+-PadB2)") (class "Default")
      (node (ref "CN15") (pin "B2") (pinfunction "TX2+_B2") (pintype "passive+no_connect"))
    )
    (net (code "83") (name "unconnected-(CN15-TX2--PadB3)") (class "Default")
      (node (ref "CN15") (pin "B3") (pinfunction "TX2-_B3") (pintype "passive+no_connect"))
    )
    (net (code "84") (name "unconnected-(U5A-GNDDetect{slash}PG5-PadK13)") (class "Default")
      (node (ref "U5") (pin "K13") (pinfunction "GNDDetect/PG5_K13") (pintype "passive+no_connect"))
    )
    (net (code "85") (name "unconnected-(U5A-HW_TYP_1{slash}PI5-PadC4)") (class "Default")
      (node (ref "U5") (pin "C4") (pinfunction "HW_TYP_1/PI5_C4") (pintype "passive+no_connect"))
    )
    (net (code "86") (name "unconnected-(U5A-T_JNRST{slash}PF13-PadN6)") (class "Default")
      (node (ref "U5") (pin "N6") (pinfunction "T_JNRST/PF13_N6") (pintype "passive+no_connect"))
    )
    (net (code "87") (name "unconnected-(U5C-CAN_RX{slash}PA11-PadC15)") (class "Default")
      (node (ref "U5") (pin "C15") (pinfunction "CAN_RX/PA11_C15") (pintype "passive+no_connect"))
    )
    (net (code "88") (name "unconnected-(U5C-CAN_TX{slash}PA12-PadB15)") (class "Default")
      (node (ref "U5") (pin "B15") (pinfunction "CAN_TX/PA12_B15") (pintype "passive+no_connect"))
    )
    (net (code "89") (name "unconnected-(U5C-GPIO0{slash}PE2-PadA2)") (class "Default")
      (node (ref "U5") (pin "A2") (pinfunction "GPIO0/PE2_A2") (pintype "passive+no_connect"))
    )
    (net (code "90") (name "unconnected-(U5C-GPIO1{slash}PE4-PadB1)") (class "Default")
      (node (ref "U5") (pin "B1") (pinfunction "GPIO1/PE4_B1") (pintype "passive+no_connect"))
    )
    (net (code "91") (name "unconnected-(U5C-I2C_SCL{slash}PB8-PadA5)") (class "Default")
      (node (ref "U5") (pin "A5") (pinfunction "I2C_SCL/PB8_A5") (pintype "passive+no_connect"))
    )
    (net (code "92") (name "unconnected-(U5C-I2C_SDA{slash}PB9-PadB4)") (class "Default")
      (node (ref "U5") (pin "B4") (pinfunction "I2C_SDA/PB9_B4") (pintype "passive+no_connect"))
    )
    (net (code "93") (name "unconnected-(U5C-SPI_MISO{slash}PC2-PadM4)") (class "Default")
      (node (ref "U5") (pin "M4") (pinfunction "SPI_MISO/PC2_M4") (pintype "passive+no_connect"))
    )
    (net (code "94") (name "unconnected-(U5C-SPI_MOSI{slash}PC1-PadM3)") (class "Default")
      (node (ref "U5") (pin "M3") (pinfunction "SPI_MOSI/PC1_M3") (pintype "passive+no_connect"))
    )
    (net (code "95") (name "unconnected-(U5C-SPI_NSS{slash}PB4-PadA9)") (class "Default")
      (node (ref "U5") (pin "A9") (pinfunction "SPI_NSS/PB4_A9") (pintype "passive+no_connect"))
    )
    (net (code "96") (name "unconnected-(U5C-SPI_SCK{slash}PA9-PadE15)") (class "Default")
      (node (ref "U5") (pin "E15") (pinfunction "SPI_SCK/PA9_E15") (pintype "passive+no_connect"))
    )
    (net (code "97") (name "unconnected-(U8-NC-Pad4)") (class "Default")
      (node (ref "U8") (pin "4") (pinfunction "NC_4") (pintype "passive+no_connect"))
    )
    (net (code "98") (name "unconnected-(U11-NC{slash}ADJ-Pad4)") (class "Default")
      (node (ref "U11") (pin "4") (pinfunction "NC/ADJ_4") (pintype "passive+no_connect"))
    )
  )
)
